# LEDs.net
KiCad netlist of a schematic drawn in EAGLE
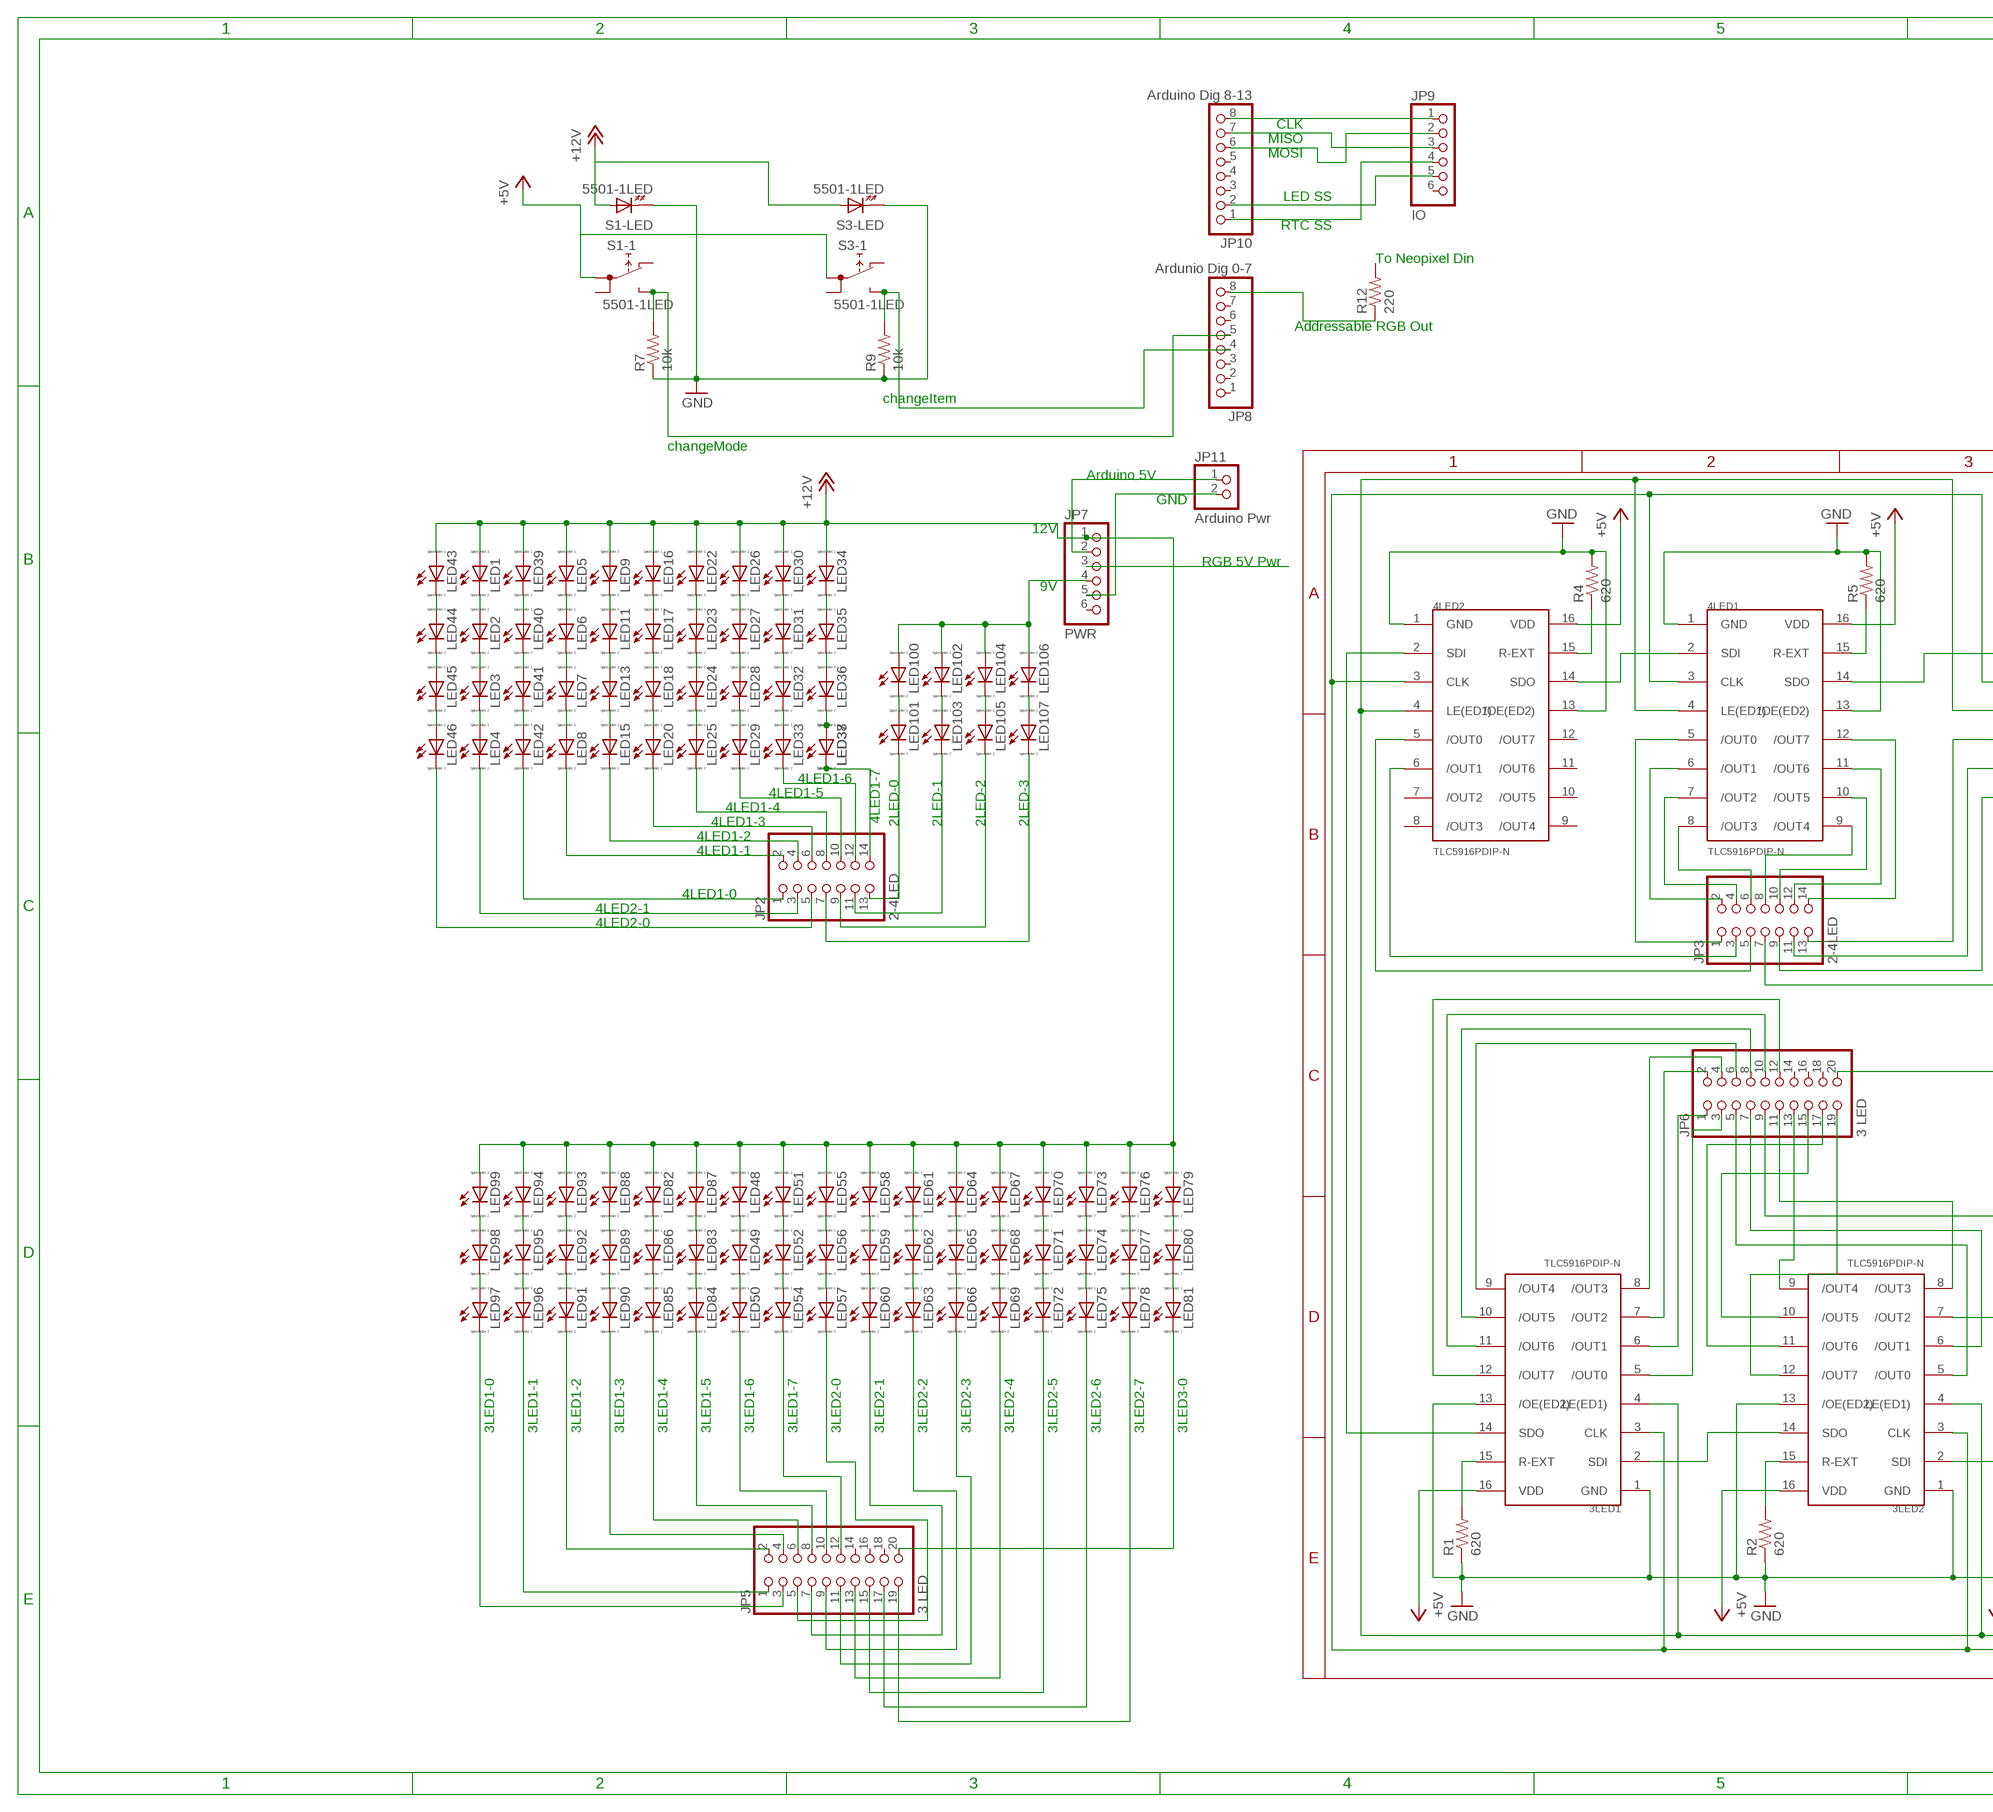
[diagram p0: schematic, sheet 1, part 1 of 2]
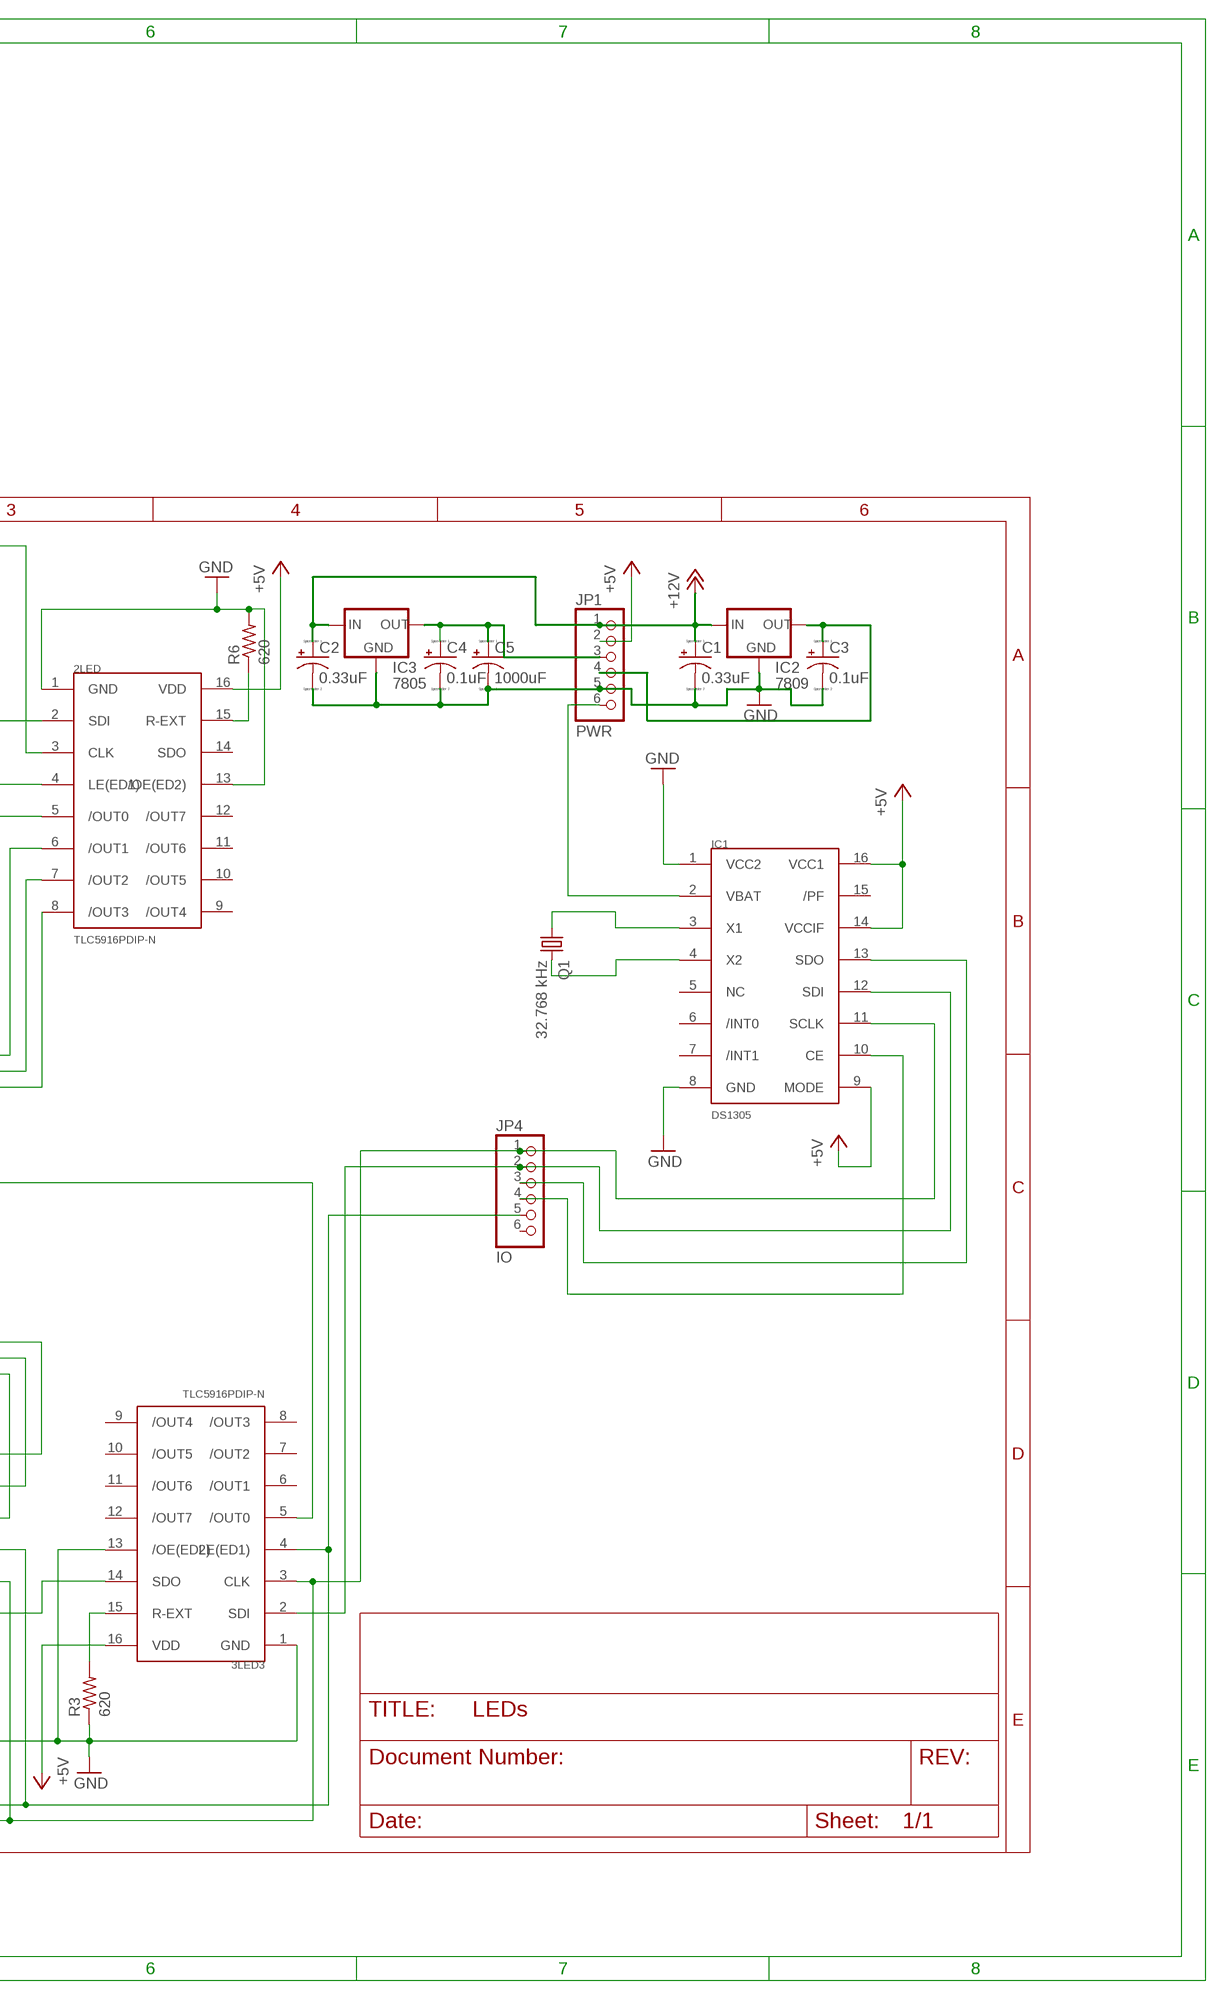
[diagram p1: schematic, sheet 1, part 2 of 2]

(export (version "E")
  (design (tool "Eeschema 10.0.6"))
  (components
    (comp (ref "2LED")
      (value "TLC5916PDIP-N")
      (footprint "eagle-import:DIL16")
      (libsource (lib "eagle-import") (part "TLC5916PDIP-N"))
    )
    (comp (ref "3LED1")
      (value "TLC5916PDIP-N")
      (footprint "eagle-import:DIL16")
      (libsource (lib "eagle-import") (part "TLC5916PDIP-N"))
    )
    (comp (ref "3LED2")
      (value "TLC5916PDIP-N")
      (footprint "eagle-import:DIL16")
      (libsource (lib "eagle-import") (part "TLC5916PDIP-N"))
    )
    (comp (ref "3LED3")
      (value "TLC5916PDIP-N")
      (footprint "eagle-import:DIL16")
      (libsource (lib "eagle-import") (part "TLC5916PDIP-N"))
    )
    (comp (ref "4LED1")
      (value "TLC5916PDIP-N")
      (footprint "eagle-import:DIL16")
      (libsource (lib "eagle-import") (part "TLC5916PDIP-N"))
    )
    (comp (ref "4LED2")
      (value "TLC5916PDIP-N")
      (footprint "eagle-import:DIL16")
      (libsource (lib "eagle-import") (part "TLC5916PDIP-N"))
    )
    (comp (ref "C1")
      (value "0.33uF")
      (footprint "eagle-import:E2-4")
      (libsource (lib "eagle-import") (part "CPOL-USE2-4"))
    )
    (comp (ref "C2")
      (value "0.33uF")
      (footprint "eagle-import:E2-4")
      (libsource (lib "eagle-import") (part "CPOL-USE2-4"))
    )
    (comp (ref "C3")
      (value "0.1uF")
      (footprint "eagle-import:E2-4")
      (libsource (lib "eagle-import") (part "CPOL-USE2-4"))
    )
    (comp (ref "C4")
      (value "0.1uF")
      (footprint "eagle-import:E2-4")
      (libsource (lib "eagle-import") (part "CPOL-USE2-4"))
    )
    (comp (ref "C5")
      (value "1000uF")
      (footprint "eagle-import:E3,5-8")
      (libsource (lib "eagle-import") (part "CPOL-USE3.5-8"))
    )
    (comp (ref "IC1")
      (value "DS1305")
      (footprint "eagle-import:DIL16")
      (libsource (lib "eagle-import") (part "DS1305"))
    )
    (comp (ref "IC2")
      (value "7809")
      (footprint "eagle-import:78XXL")
      (libsource (lib "eagle-import") (part "78XXL"))
    )
    (comp (ref "IC3")
      (value "7805")
      (footprint "eagle-import:78XXL")
      (libsource (lib "eagle-import") (part "78XXL"))
    )
    (comp (ref "JP1")
      (value "PWR")
      (footprint "eagle-import:1X06")
      (libsource (lib "eagle-import") (part "PINHD-1X6"))
    )
    (comp (ref "JP2")
      (value "2-4LED")
      (footprint "eagle-import:2X07")
      (libsource (lib "eagle-import") (part "PINHD-2X7"))
    )
    (comp (ref "JP3")
      (value "2-4LED")
      (footprint "eagle-import:2X07")
      (libsource (lib "eagle-import") (part "PINHD-2X7"))
    )
    (comp (ref "JP4")
      (value "IO")
      (footprint "eagle-import:1X06")
      (libsource (lib "eagle-import") (part "PINHD-1X6"))
    )
    (comp (ref "JP5")
      (value "3 LED")
      (footprint "eagle-import:2X10")
      (libsource (lib "eagle-import") (part "PINHD-2X10"))
    )
    (comp (ref "JP6")
      (value "3 LED")
      (footprint "eagle-import:2X10")
      (libsource (lib "eagle-import") (part "PINHD-2X10"))
    )
    (comp (ref "JP7")
      (value "PWR")
      (footprint "eagle-import:1X06")
      (libsource (lib "eagle-import") (part "PINHD-1X6"))
    )
    (comp (ref "JP8")
      (value "Ardunio Dig 0-7")
      (footprint "eagle-import:1X08")
      (libsource (lib "eagle-import") (part "PINHD-1X8"))
    )
    (comp (ref "JP9")
      (value "IO")
      (footprint "eagle-import:1X06")
      (libsource (lib "eagle-import") (part "PINHD-1X6"))
    )
    (comp (ref "JP10")
      (value "Arduino Dig 8-13")
      (footprint "eagle-import:1X08")
      (libsource (lib "eagle-import") (part "PINHD-1X8"))
    )
    (comp (ref "JP11")
      (value "Arduino Pwr")
      (footprint "eagle-import:1X02")
      (libsource (lib "eagle-import") (part "PINHD-1X2"))
    )
    (comp (ref "LED1")
      (value "LED_ELD260")
      (footprint "eagle-import:LED_LD260")
      (libsource (lib "eagle-import") (part "LED_ELD260"))
    )
    (comp (ref "LED2")
      (value "LED_ELD260")
      (footprint "eagle-import:LED_LD260")
      (libsource (lib "eagle-import") (part "LED_ELD260"))
    )
    (comp (ref "LED3")
      (value "LED_ELD260")
      (footprint "eagle-import:LED_LD260")
      (libsource (lib "eagle-import") (part "LED_ELD260"))
    )
    (comp (ref "LED4")
      (value "LED_ELD260")
      (footprint "eagle-import:LED_LD260")
      (libsource (lib "eagle-import") (part "LED_ELD260"))
    )
    (comp (ref "LED5")
      (value "LED_ELD260")
      (footprint "eagle-import:LED_LD260")
      (libsource (lib "eagle-import") (part "LED_ELD260"))
    )
    (comp (ref "LED6")
      (value "LED_ELD260")
      (footprint "eagle-import:LED_LD260")
      (libsource (lib "eagle-import") (part "LED_ELD260"))
    )
    (comp (ref "LED7")
      (value "LED_ELD260")
      (footprint "eagle-import:LED_LD260")
      (libsource (lib "eagle-import") (part "LED_ELD260"))
    )
    (comp (ref "LED8")
      (value "LED_ELD260")
      (footprint "eagle-import:LED_LD260")
      (libsource (lib "eagle-import") (part "LED_ELD260"))
    )
    (comp (ref "LED9")
      (value "LED_ELD260")
      (footprint "eagle-import:LED_LD260")
      (libsource (lib "eagle-import") (part "LED_ELD260"))
    )
    (comp (ref "LED11")
      (value "LED_ELD260")
      (footprint "eagle-import:LED_LD260")
      (libsource (lib "eagle-import") (part "LED_ELD260"))
    )
    (comp (ref "LED13")
      (value "LED_ELD260")
      (footprint "eagle-import:LED_LD260")
      (libsource (lib "eagle-import") (part "LED_ELD260"))
    )
    (comp (ref "LED15")
      (value "LED_ELD260")
      (footprint "eagle-import:LED_LD260")
      (libsource (lib "eagle-import") (part "LED_ELD260"))
    )
    (comp (ref "LED16")
      (value "LED_ELD260")
      (footprint "eagle-import:LED_LD260")
      (libsource (lib "eagle-import") (part "LED_ELD260"))
    )
    (comp (ref "LED17")
      (value "LED_ELD260")
      (footprint "eagle-import:LED_LD260")
      (libsource (lib "eagle-import") (part "LED_ELD260"))
    )
    (comp (ref "LED18")
      (value "LED_ELD260")
      (footprint "eagle-import:LED_LD260")
      (libsource (lib "eagle-import") (part "LED_ELD260"))
    )
    (comp (ref "LED20")
      (value "LED_ELD260")
      (footprint "eagle-import:LED_LD260")
      (libsource (lib "eagle-import") (part "LED_ELD260"))
    )
    (comp (ref "LED22")
      (value "LED_ELD260")
      (footprint "eagle-import:LED_LD260")
      (libsource (lib "eagle-import") (part "LED_ELD260"))
    )
    (comp (ref "LED23")
      (value "LED_ELD260")
      (footprint "eagle-import:LED_LD260")
      (libsource (lib "eagle-import") (part "LED_ELD260"))
    )
    (comp (ref "LED24")
      (value "LED_ELD260")
      (footprint "eagle-import:LED_LD260")
      (libsource (lib "eagle-import") (part "LED_ELD260"))
    )
    (comp (ref "LED25")
      (value "LED_ELD260")
      (footprint "eagle-import:LED_LD260")
      (libsource (lib "eagle-import") (part "LED_ELD260"))
    )
    (comp (ref "LED26")
      (value "LED_ELD260")
      (footprint "eagle-import:LED_LD260")
      (libsource (lib "eagle-import") (part "LED_ELD260"))
    )
    (comp (ref "LED27")
      (value "LED_ELD260")
      (footprint "eagle-import:LED_LD260")
      (libsource (lib "eagle-import") (part "LED_ELD260"))
    )
    (comp (ref "LED28")
      (value "LED_ELD260")
      (footprint "eagle-import:LED_LD260")
      (libsource (lib "eagle-import") (part "LED_ELD260"))
    )
    (comp (ref "LED29")
      (value "LED_ELD260")
      (footprint "eagle-import:LED_LD260")
      (libsource (lib "eagle-import") (part "LED_ELD260"))
    )
    (comp (ref "LED30")
      (value "LED_ELD260")
      (footprint "eagle-import:LED_LD260")
      (libsource (lib "eagle-import") (part "LED_ELD260"))
    )
    (comp (ref "LED31")
      (value "LED_ELD260")
      (footprint "eagle-import:LED_LD260")
      (libsource (lib "eagle-import") (part "LED_ELD260"))
    )
    (comp (ref "LED32")
      (value "LED_ELD260")
      (footprint "eagle-import:LED_LD260")
      (libsource (lib "eagle-import") (part "LED_ELD260"))
    )
    (comp (ref "LED33")
      (value "LED_ELD260")
      (footprint "eagle-import:LED_LD260")
      (libsource (lib "eagle-import") (part "LED_ELD260"))
    )
    (comp (ref "LED34")
      (value "LED_ELD260")
      (footprint "eagle-import:LED_LD260")
      (libsource (lib "eagle-import") (part "LED_ELD260"))
    )
    (comp (ref "LED35")
      (value "LED_ELD260")
      (footprint "eagle-import:LED_LD260")
      (libsource (lib "eagle-import") (part "LED_ELD260"))
    )
    (comp (ref "LED36")
      (value "LED_ELD260")
      (footprint "eagle-import:LED_LD260")
      (libsource (lib "eagle-import") (part "LED_ELD260"))
    )
    (comp (ref "LED37")
      (value "LED_ELD260")
      (footprint "eagle-import:LED_LD260")
      (libsource (lib "eagle-import") (part "LED_ELD260"))
    )
    (comp (ref "LED38")
      (value "LED_ELD260")
      (footprint "eagle-import:LED_LD260")
      (libsource (lib "eagle-import") (part "LED_ELD260"))
    )
    (comp (ref "LED39")
      (value "LED_ELD260")
      (footprint "eagle-import:LED_LD260")
      (libsource (lib "eagle-import") (part "LED_ELD260"))
    )
    (comp (ref "LED40")
      (value "LED_ELD260")
      (footprint "eagle-import:LED_LD260")
      (libsource (lib "eagle-import") (part "LED_ELD260"))
    )
    (comp (ref "LED41")
      (value "LED_ELD260")
      (footprint "eagle-import:LED_LD260")
      (libsource (lib "eagle-import") (part "LED_ELD260"))
    )
    (comp (ref "LED42")
      (value "LED_ELD260")
      (footprint "eagle-import:LED_LD260")
      (libsource (lib "eagle-import") (part "LED_ELD260"))
    )
    (comp (ref "LED43")
      (value "LED_ELD260")
      (footprint "eagle-import:LED_LD260")
      (libsource (lib "eagle-import") (part "LED_ELD260"))
    )
    (comp (ref "LED44")
      (value "LED_ELD260")
      (footprint "eagle-import:LED_LD260")
      (libsource (lib "eagle-import") (part "LED_ELD260"))
    )
    (comp (ref "LED45")
      (value "LED_ELD260")
      (footprint "eagle-import:LED_LD260")
      (libsource (lib "eagle-import") (part "LED_ELD260"))
    )
    (comp (ref "LED46")
      (value "LED_ELD260")
      (footprint "eagle-import:LED_LD260")
      (libsource (lib "eagle-import") (part "LED_ELD260"))
    )
    (comp (ref "LED48")
      (value "LED_ELD260")
      (footprint "eagle-import:LED_LD260")
      (libsource (lib "eagle-import") (part "LED_ELD260"))
    )
    (comp (ref "LED49")
      (value "LED_ELD260")
      (footprint "eagle-import:LED_LD260")
      (libsource (lib "eagle-import") (part "LED_ELD260"))
    )
    (comp (ref "LED50")
      (value "LED_ELD260")
      (footprint "eagle-import:LED_LD260")
      (libsource (lib "eagle-import") (part "LED_ELD260"))
    )
    (comp (ref "LED51")
      (value "LED_ELD260")
      (footprint "eagle-import:LED_LD260")
      (libsource (lib "eagle-import") (part "LED_ELD260"))
    )
    (comp (ref "LED52")
      (value "LED_ELD260")
      (footprint "eagle-import:LED_LD260")
      (libsource (lib "eagle-import") (part "LED_ELD260"))
    )
    (comp (ref "LED54")
      (value "LED_ELD260")
      (footprint "eagle-import:LED_LD260")
      (libsource (lib "eagle-import") (part "LED_ELD260"))
    )
    (comp (ref "LED55")
      (value "LED_ELD260")
      (footprint "eagle-import:LED_LD260")
      (libsource (lib "eagle-import") (part "LED_ELD260"))
    )
    (comp (ref "LED56")
      (value "LED_ELD260")
      (footprint "eagle-import:LED_LD260")
      (libsource (lib "eagle-import") (part "LED_ELD260"))
    )
    (comp (ref "LED57")
      (value "LED_ELD260")
      (footprint "eagle-import:LED_LD260")
      (libsource (lib "eagle-import") (part "LED_ELD260"))
    )
    (comp (ref "LED58")
      (value "LED_ELD260")
      (footprint "eagle-import:LED_LD260")
      (libsource (lib "eagle-import") (part "LED_ELD260"))
    )
    (comp (ref "LED59")
      (value "LED_ELD260")
      (footprint "eagle-import:LED_LD260")
      (libsource (lib "eagle-import") (part "LED_ELD260"))
    )
    (comp (ref "LED60")
      (value "LED_ELD260")
      (footprint "eagle-import:LED_LD260")
      (libsource (lib "eagle-import") (part "LED_ELD260"))
    )
    (comp (ref "LED61")
      (value "LED_ELD260")
      (footprint "eagle-import:LED_LD260")
      (libsource (lib "eagle-import") (part "LED_ELD260"))
    )
    (comp (ref "LED62")
      (value "LED_ELD260")
      (footprint "eagle-import:LED_LD260")
      (libsource (lib "eagle-import") (part "LED_ELD260"))
    )
    (comp (ref "LED63")
      (value "LED_ELD260")
      (footprint "eagle-import:LED_LD260")
      (libsource (lib "eagle-import") (part "LED_ELD260"))
    )
    (comp (ref "LED64")
      (value "LED_ELD260")
      (footprint "eagle-import:LED_LD260")
      (libsource (lib "eagle-import") (part "LED_ELD260"))
    )
    (comp (ref "LED65")
      (value "LED_ELD260")
      (footprint "eagle-import:LED_LD260")
      (libsource (lib "eagle-import") (part "LED_ELD260"))
    )
    (comp (ref "LED66")
      (value "LED_ELD260")
      (footprint "eagle-import:LED_LD260")
      (libsource (lib "eagle-import") (part "LED_ELD260"))
    )
    (comp (ref "LED67")
      (value "LED_ELD260")
      (footprint "eagle-import:LED_LD260")
      (libsource (lib "eagle-import") (part "LED_ELD260"))
    )
    (comp (ref "LED68")
      (value "LED_ELD260")
      (footprint "eagle-import:LED_LD260")
      (libsource (lib "eagle-import") (part "LED_ELD260"))
    )
    (comp (ref "LED69")
      (value "LED_ELD260")
      (footprint "eagle-import:LED_LD260")
      (libsource (lib "eagle-import") (part "LED_ELD260"))
    )
    (comp (ref "LED70")
      (value "LED_ELD260")
      (footprint "eagle-import:LED_LD260")
      (libsource (lib "eagle-import") (part "LED_ELD260"))
    )
    (comp (ref "LED71")
      (value "LED_ELD260")
      (footprint "eagle-import:LED_LD260")
      (libsource (lib "eagle-import") (part "LED_ELD260"))
    )
    (comp (ref "LED72")
      (value "LED_ELD260")
      (footprint "eagle-import:LED_LD260")
      (libsource (lib "eagle-import") (part "LED_ELD260"))
    )
    (comp (ref "LED73")
      (value "LED_ELD260")
      (footprint "eagle-import:LED_LD260")
      (libsource (lib "eagle-import") (part "LED_ELD260"))
    )
    (comp (ref "LED74")
      (value "LED_ELD260")
      (footprint "eagle-import:LED_LD260")
      (libsource (lib "eagle-import") (part "LED_ELD260"))
    )
    (comp (ref "LED75")
      (value "LED_ELD260")
      (footprint "eagle-import:LED_LD260")
      (libsource (lib "eagle-import") (part "LED_ELD260"))
    )
    (comp (ref "LED76")
      (value "LED_ELD260")
      (footprint "eagle-import:LED_LD260")
      (libsource (lib "eagle-import") (part "LED_ELD260"))
    )
    (comp (ref "LED77")
      (value "LED_ELD260")
      (footprint "eagle-import:LED_LD260")
      (libsource (lib "eagle-import") (part "LED_ELD260"))
    )
    (comp (ref "LED78")
      (value "LED_ELD260")
      (footprint "eagle-import:LED_LD260")
      (libsource (lib "eagle-import") (part "LED_ELD260"))
    )
    (comp (ref "LED79")
      (value "LED_ELD260")
      (footprint "eagle-import:LED_LD260")
      (libsource (lib "eagle-import") (part "LED_ELD260"))
    )
    (comp (ref "LED80")
      (value "LED_ELD260")
      (footprint "eagle-import:LED_LD260")
      (libsource (lib "eagle-import") (part "LED_ELD260"))
    )
    (comp (ref "LED81")
      (value "LED_ELD260")
      (footprint "eagle-import:LED_LD260")
      (libsource (lib "eagle-import") (part "LED_ELD260"))
    )
    (comp (ref "LED82")
      (value "LED_ELD260")
      (footprint "eagle-import:LED_LD260")
      (libsource (lib "eagle-import") (part "LED_ELD260"))
    )
    (comp (ref "LED83")
      (value "LED_ELD260")
      (footprint "eagle-import:LED_LD260")
      (libsource (lib "eagle-import") (part "LED_ELD260"))
    )
    (comp (ref "LED84")
      (value "LED_ELD260")
      (footprint "eagle-import:LED_LD260")
      (libsource (lib "eagle-import") (part "LED_ELD260"))
    )
    (comp (ref "LED85")
      (value "LED_ELD260")
      (footprint "eagle-import:LED_LD260")
      (libsource (lib "eagle-import") (part "LED_ELD260"))
    )
    (comp (ref "LED86")
      (value "LED_ELD260")
      (footprint "eagle-import:LED_LD260")
      (libsource (lib "eagle-import") (part "LED_ELD260"))
    )
    (comp (ref "LED87")
      (value "LED_ELD260")
      (footprint "eagle-import:LED_LD260")
      (libsource (lib "eagle-import") (part "LED_ELD260"))
    )
    (comp (ref "LED88")
      (value "LED_ELD260")
      (footprint "eagle-import:LED_LD260")
      (libsource (lib "eagle-import") (part "LED_ELD260"))
    )
    (comp (ref "LED89")
      (value "LED_ELD260")
      (footprint "eagle-import:LED_LD260")
      (libsource (lib "eagle-import") (part "LED_ELD260"))
    )
    (comp (ref "LED90")
      (value "LED_ELD260")
      (footprint "eagle-import:LED_LD260")
      (libsource (lib "eagle-import") (part "LED_ELD260"))
    )
    (comp (ref "LED91")
      (value "LED_ELD260")
      (footprint "eagle-import:LED_LD260")
      (libsource (lib "eagle-import") (part "LED_ELD260"))
    )
    (comp (ref "LED92")
      (value "LED_ELD260")
      (footprint "eagle-import:LED_LD260")
      (libsource (lib "eagle-import") (part "LED_ELD260"))
    )
    (comp (ref "LED93")
      (value "LED_ELD260")
      (footprint "eagle-import:LED_LD260")
      (libsource (lib "eagle-import") (part "LED_ELD260"))
    )
    (comp (ref "LED94")
      (value "LED_ELD260")
      (footprint "eagle-import:LED_LD260")
      (libsource (lib "eagle-import") (part "LED_ELD260"))
    )
    (comp (ref "LED95")
      (value "LED_ELD260")
      (footprint "eagle-import:LED_LD260")
      (libsource (lib "eagle-import") (part "LED_ELD260"))
    )
    (comp (ref "LED96")
      (value "LED_ELD260")
      (footprint "eagle-import:LED_LD260")
      (libsource (lib "eagle-import") (part "LED_ELD260"))
    )
    (comp (ref "LED97")
      (value "LED_ELD260")
      (footprint "eagle-import:LED_LD260")
      (libsource (lib "eagle-import") (part "LED_ELD260"))
    )
    (comp (ref "LED98")
      (value "LED_ELD260")
      (footprint "eagle-import:LED_LD260")
      (libsource (lib "eagle-import") (part "LED_ELD260"))
    )
    (comp (ref "LED99")
      (value "LED_ELD260")
      (footprint "eagle-import:LED_LD260")
      (libsource (lib "eagle-import") (part "LED_ELD260"))
    )
    (comp (ref "LED100")
      (value "LED_ELD260")
      (footprint "eagle-import:LED_LD260")
      (libsource (lib "eagle-import") (part "LED_ELD260"))
    )
    (comp (ref "LED101")
      (value "LED_ELD260")
      (footprint "eagle-import:LED_LD260")
      (libsource (lib "eagle-import") (part "LED_ELD260"))
    )
    (comp (ref "LED102")
      (value "LED_ELD260")
      (footprint "eagle-import:LED_LD260")
      (libsource (lib "eagle-import") (part "LED_ELD260"))
    )
    (comp (ref "LED103")
      (value "LED_ELD260")
      (footprint "eagle-import:LED_LD260")
      (libsource (lib "eagle-import") (part "LED_ELD260"))
    )
    (comp (ref "LED104")
      (value "LED_ELD260")
      (footprint "eagle-import:LED_LD260")
      (libsource (lib "eagle-import") (part "LED_ELD260"))
    )
    (comp (ref "LED105")
      (value "LED_ELD260")
      (footprint "eagle-import:LED_LD260")
      (libsource (lib "eagle-import") (part "LED_ELD260"))
    )
    (comp (ref "LED106")
      (value "LED_ELD260")
      (footprint "eagle-import:LED_LD260")
      (libsource (lib "eagle-import") (part "LED_ELD260"))
    )
    (comp (ref "LED107")
      (value "LED_ELD260")
      (footprint "eagle-import:LED_LD260")
      (libsource (lib "eagle-import") (part "LED_ELD260"))
    )
    (comp (ref "Q1")
      (value "32.768 kHz")
      (footprint "eagle-import:TC26V")
      (libsource (lib "eagle-import") (part "CRYSTALTC26V"))
    )
    (comp (ref "R1")
      (value "620")
      (footprint "eagle-import:V235_17")
      (libsource (lib "eagle-import") (part "R-US_V235/17"))
    )
    (comp (ref "R2")
      (value "620")
      (footprint "eagle-import:V235_17")
      (libsource (lib "eagle-import") (part "R-US_V235/17"))
    )
    (comp (ref "R3")
      (value "620")
      (footprint "eagle-import:V235_17")
      (libsource (lib "eagle-import") (part "R-US_V235/17"))
    )
    (comp (ref "R4")
      (value "620")
      (footprint "eagle-import:V235_17")
      (libsource (lib "eagle-import") (part "R-US_V235/17"))
    )
    (comp (ref "R5")
      (value "620")
      (footprint "eagle-import:V235_17")
      (libsource (lib "eagle-import") (part "R-US_V235/17"))
    )
    (comp (ref "R6")
      (value "620")
      (footprint "eagle-import:V235_17")
      (libsource (lib "eagle-import") (part "R-US_V235/17"))
    )
    (comp (ref "R7")
      (value "10k")
      (footprint "eagle-import:0204_7")
      (libsource (lib "eagle-import") (part "R-US_0204/7"))
    )
    (comp (ref "R9")
      (value "10k")
      (footprint "eagle-import:0204_7")
      (libsource (lib "eagle-import") (part "R-US_0204/7"))
    )
    (comp (ref "R12")
      (value "220")
      (footprint "eagle-import:0204_7")
      (libsource (lib "eagle-import") (part "R-US_0204/7"))
    )
    (comp (ref "S1")
      (value "5501-1LED")
      (footprint "eagle-import:5501-1LED")
      (libsource (lib "eagle-import") (part "55?-1LED01"))
    )
    (comp (ref "S3")
      (value "5501-1LED")
      (footprint "eagle-import:5501-1LED")
      (libsource (lib "eagle-import") (part "55?-1LED01"))
    )
  )
  (nets
    (net (code "1") (name "+5V") (class "Default")
      (node (ref "2LED") (pin "16") (pinfunction "VDD_16") (pintype "power_in"))
      (node (ref "3LED1") (pin "16") (pinfunction "VDD_16") (pintype "power_in"))
      (node (ref "3LED2") (pin "16") (pinfunction "VDD_16") (pintype "power_in"))
      (node (ref "3LED3") (pin "16") (pinfunction "VDD_16") (pintype "power_in"))
      (node (ref "4LED1") (pin "16") (pinfunction "VDD_16") (pintype "power_in"))
      (node (ref "4LED2") (pin "16") (pinfunction "VDD_16") (pintype "power_in"))
      (node (ref "IC1") (pin "14") (pinfunction "VCCIF_14") (pintype "power_in"))
      (node (ref "IC1") (pin "16") (pinfunction "VCC1_16") (pintype "power_in"))
      (node (ref "IC1") (pin "9") (pinfunction "MODE_9") (pintype "input"))
      (node (ref "JP1") (pin "2") (pinfunction "2_2") (pintype "passive"))
      (node (ref "S1") (pin "1A") (pinfunction "1A_1A") (pintype "passive"))
      (node (ref "S3") (pin "1A") (pinfunction "1A_1A") (pintype "passive"))
    )
    (net (code "2") (name "+12V") (class "Default")
      (node (ref "C1") (pin "+") (pinfunction "+_+") (pintype "passive"))
      (node (ref "C2") (pin "+") (pinfunction "+_+") (pintype "passive"))
      (node (ref "IC2") (pin "IN") (pinfunction "IN_IN") (pintype "input"))
      (node (ref "IC3") (pin "IN") (pinfunction "IN_IN") (pintype "input"))
      (node (ref "JP1") (pin "1") (pinfunction "1_1") (pintype "passive"))
      (node (ref "JP7") (pin "1") (pinfunction "1_1") (pintype "passive"))
      (node (ref "LED1") (pin "A") (pinfunction "A_A") (pintype "passive"))
      (node (ref "LED16") (pin "A") (pinfunction "A_A") (pintype "passive"))
      (node (ref "LED22") (pin "A") (pinfunction "A_A") (pintype "passive"))
      (node (ref "LED26") (pin "A") (pinfunction "A_A") (pintype "passive"))
      (node (ref "LED30") (pin "A") (pinfunction "A_A") (pintype "passive"))
      (node (ref "LED34") (pin "A") (pinfunction "A_A") (pintype "passive"))
      (node (ref "LED39") (pin "A") (pinfunction "A_A") (pintype "passive"))
      (node (ref "LED43") (pin "A") (pinfunction "A_A") (pintype "passive"))
      (node (ref "LED48") (pin "A") (pinfunction "A_A") (pintype "passive"))
      (node (ref "LED5") (pin "A") (pinfunction "A_A") (pintype "passive"))
      (node (ref "LED51") (pin "A") (pinfunction "A_A") (pintype "passive"))
      (node (ref "LED55") (pin "A") (pinfunction "A_A") (pintype "passive"))
      (node (ref "LED58") (pin "A") (pinfunction "A_A") (pintype "passive"))
      (node (ref "LED61") (pin "A") (pinfunction "A_A") (pintype "passive"))
      (node (ref "LED64") (pin "A") (pinfunction "A_A") (pintype "passive"))
      (node (ref "LED67") (pin "A") (pinfunction "A_A") (pintype "passive"))
      (node (ref "LED70") (pin "A") (pinfunction "A_A") (pintype "passive"))
      (node (ref "LED73") (pin "A") (pinfunction "A_A") (pintype "passive"))
      (node (ref "LED76") (pin "A") (pinfunction "A_A") (pintype "passive"))
      (node (ref "LED79") (pin "A") (pinfunction "A_A") (pintype "passive"))
      (node (ref "LED82") (pin "A") (pinfunction "A_A") (pintype "passive"))
      (node (ref "LED87") (pin "A") (pinfunction "A_A") (pintype "passive"))
      (node (ref "LED88") (pin "A") (pinfunction "A_A") (pintype "passive"))
      (node (ref "LED9") (pin "A") (pinfunction "A_A") (pintype "passive"))
      (node (ref "LED93") (pin "A") (pinfunction "A_A") (pintype "passive"))
      (node (ref "LED94") (pin "A") (pinfunction "A_A") (pintype "passive"))
      (node (ref "LED99") (pin "A") (pinfunction "A_A") (pintype "passive"))
      (node (ref "S1") (pin "+") (pinfunction "A_+") (pintype "passive"))
      (node (ref "S3") (pin "+") (pinfunction "A_+") (pintype "passive"))
    )
    (net (code "3") (name "GND") (class "Default")
      (node (ref "2LED") (pin "1") (pinfunction "GND_1") (pintype "power_in"))
      (node (ref "2LED") (pin "13") (pinfunction "/OE(ED2)_13") (pintype "input"))
      (node (ref "3LED1") (pin "1") (pinfunction "GND_1") (pintype "power_in"))
      (node (ref "3LED1") (pin "13") (pinfunction "/OE(ED2)_13") (pintype "input"))
      (node (ref "3LED2") (pin "1") (pinfunction "GND_1") (pintype "power_in"))
      (node (ref "3LED2") (pin "13") (pinfunction "/OE(ED2)_13") (pintype "input"))
      (node (ref "3LED3") (pin "1") (pinfunction "GND_1") (pintype "power_in"))
      (node (ref "3LED3") (pin "13") (pinfunction "/OE(ED2)_13") (pintype "input"))
      (node (ref "4LED1") (pin "1") (pinfunction "GND_1") (pintype "power_in"))
      (node (ref "4LED1") (pin "13") (pinfunction "/OE(ED2)_13") (pintype "input"))
      (node (ref "4LED2") (pin "1") (pinfunction "GND_1") (pintype "power_in"))
      (node (ref "4LED2") (pin "13") (pinfunction "/OE(ED2)_13") (pintype "input"))
      (node (ref "C1") (pin "-") (pinfunction "-_-") (pintype "passive"))
      (node (ref "C2") (pin "-") (pinfunction "-_-") (pintype "passive"))
      (node (ref "C3") (pin "-") (pinfunction "-_-") (pintype "passive"))
      (node (ref "C4") (pin "-") (pinfunction "-_-") (pintype "passive"))
      (node (ref "C5") (pin "-") (pinfunction "-_-") (pintype "passive"))
      (node (ref "IC1") (pin "1") (pinfunction "VCC2_1") (pintype "power_in"))
      (node (ref "IC1") (pin "8") (pinfunction "GND_8") (pintype "power_in"))
      (node (ref "IC2") (pin "GND") (pinfunction "GND_GND") (pintype "input"))
      (node (ref "IC3") (pin "GND") (pinfunction "GND_GND") (pintype "input"))
      (node (ref "JP1") (pin "5") (pinfunction "5_5") (pintype "passive"))
      (node (ref "R1") (pin "1") (pinfunction "1_1") (pintype "passive"))
      (node (ref "R2") (pin "1") (pinfunction "1_1") (pintype "passive"))
      (node (ref "R3") (pin "1") (pinfunction "1_1") (pintype "passive"))
      (node (ref "R4") (pin "2") (pinfunction "2_2") (pintype "passive"))
      (node (ref "R5") (pin "2") (pinfunction "2_2") (pintype "passive"))
      (node (ref "R6") (pin "2") (pinfunction "2_2") (pintype "passive"))
      (node (ref "R7") (pin "1") (pinfunction "1_1") (pintype "passive"))
      (node (ref "R9") (pin "1") (pinfunction "1_1") (pintype "passive"))
      (node (ref "S1") (pin "-") (pinfunction "K_-") (pintype "passive"))
      (node (ref "S3") (pin "-") (pinfunction "K_-") (pintype "passive"))
    )
    (net (code "4") (name "Net-(2LED-CLK)") (class "Default")
      (node (ref "2LED") (pin "3") (pinfunction "CLK_3") (pintype "input"))
      (node (ref "3LED1") (pin "3") (pinfunction "CLK_3") (pintype "input"))
      (node (ref "3LED2") (pin "3") (pinfunction "CLK_3") (pintype "input"))
      (node (ref "3LED3") (pin "3") (pinfunction "CLK_3") (pintype "input"))
      (node (ref "4LED1") (pin "3") (pinfunction "CLK_3") (pintype "input"))
      (node (ref "4LED2") (pin "3") (pinfunction "CLK_3") (pintype "input"))
      (node (ref "IC1") (pin "11") (pinfunction "SCLK_11") (pintype "input"))
      (node (ref "JP4") (pin "1") (pinfunction "1_1") (pintype "passive"))
    )
    (net (code "5") (name "Net-(2LED-LE(ED1))") (class "Default")
      (node (ref "2LED") (pin "4") (pinfunction "LE(ED1)_4") (pintype "input"))
      (node (ref "3LED1") (pin "4") (pinfunction "LE(ED1)_4") (pintype "input"))
      (node (ref "3LED2") (pin "4") (pinfunction "LE(ED1)_4") (pintype "input"))
      (node (ref "3LED3") (pin "4") (pinfunction "LE(ED1)_4") (pintype "input"))
      (node (ref "4LED1") (pin "4") (pinfunction "LE(ED1)_4") (pintype "input"))
      (node (ref "4LED2") (pin "4") (pinfunction "LE(ED1)_4") (pintype "input"))
      (node (ref "JP4") (pin "5") (pinfunction "5_5") (pintype "passive"))
    )
    (net (code "6") (name "Net-(2LED-R-EXT)") (class "Default")
      (node (ref "2LED") (pin "15") (pinfunction "R-EXT_15") (pintype "output"))
      (node (ref "R6") (pin "1") (pinfunction "1_1") (pintype "passive"))
    )
    (net (code "7") (name "Net-(2LED-SDI)") (class "Default")
      (node (ref "2LED") (pin "2") (pinfunction "SDI_2") (pintype "bidirectional"))
      (node (ref "4LED1") (pin "14") (pinfunction "SDO_14") (pintype "bidirectional"))
    )
    (net (code "8") (name "Net-(2LED-{slash}OUT0)") (class "Default")
      (node (ref "2LED") (pin "5") (pinfunction "/OUT0_5") (pintype "output"))
      (node (ref "JP3") (pin "13") (pinfunction "13_13") (pintype "passive"))
    )
    (net (code "9") (name "Net-(2LED-{slash}OUT1)") (class "Default")
      (node (ref "2LED") (pin "6") (pinfunction "/OUT1_6") (pintype "output"))
      (node (ref "JP3") (pin "11") (pinfunction "11_11") (pintype "passive"))
    )
    (net (code "10") (name "Net-(2LED-{slash}OUT2)") (class "Default")
      (node (ref "2LED") (pin "7") (pinfunction "/OUT2_7") (pintype "output"))
      (node (ref "JP3") (pin "9") (pinfunction "9_9") (pintype "passive"))
    )
    (net (code "11") (name "Net-(2LED-{slash}OUT3)") (class "Default")
      (node (ref "2LED") (pin "8") (pinfunction "/OUT3_8") (pintype "output"))
      (node (ref "JP3") (pin "7") (pinfunction "7_7") (pintype "passive"))
    )
    (net (code "12") (name "Net-(3LED1-R-EXT)") (class "Default")
      (node (ref "3LED1") (pin "15") (pinfunction "R-EXT_15") (pintype "output"))
      (node (ref "R1") (pin "2") (pinfunction "2_2") (pintype "passive"))
    )
    (net (code "13") (name "Net-(3LED1-SDI)") (class "Default")
      (node (ref "3LED1") (pin "2") (pinfunction "SDI_2") (pintype "bidirectional"))
      (node (ref "3LED2") (pin "14") (pinfunction "SDO_14") (pintype "bidirectional"))
    )
    (net (code "14") (name "Net-(3LED1-SDO)") (class "Default")
      (node (ref "3LED1") (pin "14") (pinfunction "SDO_14") (pintype "bidirectional"))
      (node (ref "4LED2") (pin "2") (pinfunction "SDI_2") (pintype "bidirectional"))
    )
    (net (code "15") (name "Net-(3LED1-{slash}OUT0)") (class "Default")
      (node (ref "3LED1") (pin "5") (pinfunction "/OUT0_5") (pintype "output"))
      (node (ref "JP6") (pin "3") (pinfunction "3_3") (pintype "passive"))
    )
    (net (code "16") (name "Net-(3LED1-{slash}OUT1)") (class "Default")
      (node (ref "3LED1") (pin "6") (pinfunction "/OUT1_6") (pintype "output"))
      (node (ref "JP6") (pin "1") (pinfunction "1_1") (pintype "passive"))
    )
    (net (code "17") (name "Net-(3LED1-{slash}OUT2)") (class "Default")
      (node (ref "3LED1") (pin "7") (pinfunction "/OUT2_7") (pintype "output"))
      (node (ref "JP6") (pin "2") (pinfunction "2_2") (pintype "passive"))
    )
    (net (code "18") (name "Net-(3LED1-{slash}OUT3)") (class "Default")
      (node (ref "3LED1") (pin "8") (pinfunction "/OUT3_8") (pintype "output"))
      (node (ref "JP6") (pin "4") (pinfunction "4_4") (pintype "passive"))
    )
    (net (code "19") (name "Net-(3LED1-{slash}OUT4)") (class "Default")
      (node (ref "3LED1") (pin "9") (pinfunction "/OUT4_9") (pintype "output"))
      (node (ref "JP6") (pin "6") (pinfunction "6_6") (pintype "passive"))
    )
    (net (code "20") (name "Net-(3LED1-{slash}OUT5)") (class "Default")
      (node (ref "3LED1") (pin "10") (pinfunction "/OUT5_10") (pintype "output"))
      (node (ref "JP6") (pin "8") (pinfunction "8_8") (pintype "passive"))
    )
    (net (code "21") (name "Net-(3LED1-{slash}OUT6)") (class "Default")
      (node (ref "3LED1") (pin "11") (pinfunction "/OUT6_11") (pintype "output"))
      (node (ref "JP6") (pin "10") (pinfunction "10_10") (pintype "passive"))
    )
    (net (code "22") (name "Net-(3LED1-{slash}OUT7)") (class "Default")
      (node (ref "3LED1") (pin "12") (pinfunction "/OUT7_12") (pintype "output"))
      (node (ref "JP6") (pin "12") (pinfunction "12_12") (pintype "passive"))
    )
    (net (code "23") (name "Net-(3LED2-R-EXT)") (class "Default")
      (node (ref "3LED2") (pin "15") (pinfunction "R-EXT_15") (pintype "output"))
      (node (ref "R2") (pin "2") (pinfunction "2_2") (pintype "passive"))
    )
    (net (code "24") (name "Net-(3LED2-SDI)") (class "Default")
      (node (ref "3LED2") (pin "2") (pinfunction "SDI_2") (pintype "bidirectional"))
      (node (ref "3LED3") (pin "14") (pinfunction "SDO_14") (pintype "bidirectional"))
    )
    (net (code "25") (name "Net-(3LED2-{slash}OUT0)") (class "Default")
      (node (ref "3LED2") (pin "5") (pinfunction "/OUT0_5") (pintype "output"))
      (node (ref "JP6") (pin "5") (pinfunction "5_5") (pintype "passive"))
    )
    (net (code "26") (name "Net-(3LED2-{slash}OUT1)") (class "Default")
      (node (ref "3LED2") (pin "6") (pinfunction "/OUT1_6") (pintype "output"))
      (node (ref "JP6") (pin "7") (pinfunction "7_7") (pintype "passive"))
    )
    (net (code "27") (name "Net-(3LED2-{slash}OUT2)") (class "Default")
      (node (ref "3LED2") (pin "7") (pinfunction "/OUT2_7") (pintype "output"))
      (node (ref "JP6") (pin "9") (pinfunction "9_9") (pintype "passive"))
    )
    (net (code "28") (name "Net-(3LED2-{slash}OUT3)") (class "Default")
      (node (ref "3LED2") (pin "8") (pinfunction "/OUT3_8") (pintype "output"))
      (node (ref "JP6") (pin "11") (pinfunction "11_11") (pintype "passive"))
    )
    (net (code "29") (name "Net-(3LED2-{slash}OUT4)") (class "Default")
      (node (ref "3LED2") (pin "9") (pinfunction "/OUT4_9") (pintype "output"))
      (node (ref "JP6") (pin "13") (pinfunction "13_13") (pintype "passive"))
    )
    (net (code "30") (name "Net-(3LED2-{slash}OUT5)") (class "Default")
      (node (ref "3LED2") (pin "10") (pinfunction "/OUT5_10") (pintype "output"))
      (node (ref "JP6") (pin "15") (pinfunction "15_15") (pintype "passive"))
    )
    (net (code "31") (name "Net-(3LED2-{slash}OUT6)") (class "Default")
      (node (ref "3LED2") (pin "11") (pinfunction "/OUT6_11") (pintype "output"))
      (node (ref "JP6") (pin "17") (pinfunction "17_17") (pintype "passive"))
    )
    (net (code "32") (name "Net-(3LED2-{slash}OUT7)") (class "Default")
      (node (ref "3LED2") (pin "12") (pinfunction "/OUT7_12") (pintype "output"))
      (node (ref "JP6") (pin "19") (pinfunction "19_19") (pintype "passive"))
    )
    (net (code "33") (name "Net-(3LED3-R-EXT)") (class "Default")
      (node (ref "3LED3") (pin "15") (pinfunction "R-EXT_15") (pintype "output"))
      (node (ref "R3") (pin "2") (pinfunction "2_2") (pintype "passive"))
    )
    (net (code "34") (name "Net-(3LED3-SDI)") (class "Default")
      (node (ref "3LED3") (pin "2") (pinfunction "SDI_2") (pintype "bidirectional"))
      (node (ref "IC1") (pin "12") (pinfunction "SDI_12") (pintype "input"))
      (node (ref "JP4") (pin "2") (pinfunction "2_2") (pintype "passive"))
    )
    (net (code "35") (name "Net-(3LED3-{slash}OUT0)") (class "Default")
      (node (ref "3LED3") (pin "5") (pinfunction "/OUT0_5") (pintype "output"))
      (node (ref "JP6") (pin "20") (pinfunction "20_20") (pintype "passive"))
    )
    (net (code "36") (name "Net-(4LED1-R-EXT)") (class "Default")
      (node (ref "4LED1") (pin "15") (pinfunction "R-EXT_15") (pintype "output"))
      (node (ref "R5") (pin "1") (pinfunction "1_1") (pintype "passive"))
    )
    (net (code "37") (name "Net-(4LED1-SDI)") (class "Default")
      (node (ref "4LED1") (pin "2") (pinfunction "SDI_2") (pintype "bidirectional"))
      (node (ref "4LED2") (pin "14") (pinfunction "SDO_14") (pintype "bidirectional"))
    )
    (net (code "38") (name "Net-(4LED1-{slash}OUT0)") (class "Default")
      (node (ref "4LED1") (pin "5") (pinfunction "/OUT0_5") (pintype "output"))
      (node (ref "JP3") (pin "1") (pinfunction "1_1") (pintype "passive"))
    )
    (net (code "39") (name "Net-(4LED1-{slash}OUT1)") (class "Default")
      (node (ref "4LED1") (pin "6") (pinfunction "/OUT1_6") (pintype "output"))
      (node (ref "JP3") (pin "2") (pinfunction "2_2") (pintype "passive"))
    )
    (net (code "40") (name "Net-(4LED1-{slash}OUT2)") (class "Default")
      (node (ref "4LED1") (pin "7") (pinfunction "/OUT2_7") (pintype "output"))
      (node (ref "JP3") (pin "4") (pinfunction "4_4") (pintype "passive"))
    )
    (net (code "41") (name "Net-(4LED1-{slash}OUT3)") (class "Default")
      (node (ref "4LED1") (pin "8") (pinfunction "/OUT3_8") (pintype "output"))
      (node (ref "JP3") (pin "6") (pinfunction "6_6") (pintype "passive"))
    )
    (net (code "42") (name "Net-(4LED1-{slash}OUT4)") (class "Default")
      (node (ref "4LED1") (pin "9") (pinfunction "/OUT4_9") (pintype "output"))
      (node (ref "JP3") (pin "8") (pinfunction "8_8") (pintype "passive"))
    )
    (net (code "43") (name "Net-(4LED1-{slash}OUT5)") (class "Default")
      (node (ref "4LED1") (pin "10") (pinfunction "/OUT5_10") (pintype "output"))
      (node (ref "JP3") (pin "10") (pinfunction "10_10") (pintype "passive"))
    )
    (net (code "44") (name "Net-(4LED1-{slash}OUT6)") (class "Default")
      (node (ref "4LED1") (pin "11") (pinfunction "/OUT6_11") (pintype "output"))
      (node (ref "JP3") (pin "12") (pinfunction "12_12") (pintype "passive"))
    )
    (net (code "45") (name "Net-(4LED1-{slash}OUT7)") (class "Default")
      (node (ref "4LED1") (pin "12") (pinfunction "/OUT7_12") (pintype "output"))
      (node (ref "JP3") (pin "14") (pinfunction "14_14") (pintype "passive"))
    )
    (net (code "46") (name "Net-(4LED2-R-EXT)") (class "Default")
      (node (ref "4LED2") (pin "15") (pinfunction "R-EXT_15") (pintype "output"))
      (node (ref "R4") (pin "1") (pinfunction "1_1") (pintype "passive"))
    )
    (net (code "47") (name "Net-(4LED2-{slash}OUT0)") (class "Default")
      (node (ref "4LED2") (pin "5") (pinfunction "/OUT0_5") (pintype "output"))
      (node (ref "JP3") (pin "5") (pinfunction "5_5") (pintype "passive"))
    )
    (net (code "48") (name "Net-(4LED2-{slash}OUT1)") (class "Default")
      (node (ref "4LED2") (pin "6") (pinfunction "/OUT1_6") (pintype "output"))
      (node (ref "JP3") (pin "3") (pinfunction "3_3") (pintype "passive"))
    )
    (net (code "49") (name "Net-(C3-Pad+)") (class "Default")
      (node (ref "C3") (pin "+") (pinfunction "+_+") (pintype "passive"))
      (node (ref "IC2") (pin "OUT") (pinfunction "OUT_OUT") (pintype "passive"))
      (node (ref "JP1") (pin "4") (pinfunction "4_4") (pintype "passive"))
    )
    (net (code "50") (name "Net-(C4-Pad+)") (class "Default")
      (node (ref "C4") (pin "+") (pinfunction "+_+") (pintype "passive"))
      (node (ref "C5") (pin "+") (pinfunction "+_+") (pintype "passive"))
      (node (ref "IC3") (pin "OUT") (pinfunction "OUT_OUT") (pintype "passive"))
      (node (ref "JP1") (pin "3") (pinfunction "3_3") (pintype "passive"))
    )
    (net (code "51") (name "Net-(IC1-CE)") (class "Default")
      (node (ref "IC1") (pin "10") (pinfunction "CE_10") (pintype "input"))
      (node (ref "JP4") (pin "4") (pinfunction "4_4") (pintype "passive"))
    )
    (net (code "52") (name "Net-(IC1-SDO)") (class "Default")
      (node (ref "IC1") (pin "13") (pinfunction "SDO_13") (pintype "output"))
      (node (ref "JP4") (pin "3") (pinfunction "3_3") (pintype "passive"))
    )
    (net (code "53") (name "Net-(IC1-VBAT)") (class "Default")
      (node (ref "IC1") (pin "2") (pinfunction "VBAT_2") (pintype "power_in"))
      (node (ref "JP1") (pin "6") (pinfunction "6_6") (pintype "passive"))
    )
    (net (code "54") (name "Net-(IC1-X1)") (class "Default")
      (node (ref "IC1") (pin "3") (pinfunction "X1_3") (pintype "input"))
      (node (ref "Q1") (pin "1") (pinfunction "1_1") (pintype "passive"))
    )
    (net (code "55") (name "Net-(IC1-X2)") (class "Default")
      (node (ref "IC1") (pin "4") (pinfunction "X2_4") (pintype "output"))
      (node (ref "Q1") (pin "2") (pinfunction "2_2") (pintype "passive"))
    )
    (net (code "56") (name "Net-(JP7-Pad4)") (class "Default")
      (node (ref "JP7") (pin "4") (pinfunction "4_4") (pintype "passive"))
      (node (ref "LED100") (pin "A") (pinfunction "A_A") (pintype "passive"))
      (node (ref "LED102") (pin "A") (pinfunction "A_A") (pintype "passive"))
      (node (ref "LED104") (pin "A") (pinfunction "A_A") (pintype "passive"))
      (node (ref "LED106") (pin "A") (pinfunction "A_A") (pintype "passive"))
    )
    (net (code "57") (name "Net-(JP8-Pad4)") (class "Default")
      (node (ref "JP8") (pin "4") (pinfunction "4_4") (pintype "passive"))
      (node (ref "R9") (pin "2") (pinfunction "2_2") (pintype "passive"))
      (node (ref "S3") (pin "NO") (pinfunction "NO_NO") (pintype "passive"))
    )
    (net (code "58") (name "Net-(JP8-Pad5)") (class "Default")
      (node (ref "JP8") (pin "5") (pinfunction "5_5") (pintype "passive"))
      (node (ref "R7") (pin "2") (pinfunction "2_2") (pintype "passive"))
      (node (ref "S1") (pin "NO") (pinfunction "NO_NO") (pintype "passive"))
    )
    (net (code "59") (name "Net-(JP8-Pad8)") (class "Default")
      (node (ref "JP8") (pin "8") (pinfunction "8_8") (pintype "passive"))
      (node (ref "R12") (pin "1") (pinfunction "1_1") (pintype "passive"))
    )
    (net (code "60") (name "Net-(JP10-Pad1)") (class "Default")
      (node (ref "JP10") (pin "1") (pinfunction "1_1") (pintype "passive"))
      (node (ref "JP9") (pin "4") (pinfunction "4_4") (pintype "passive"))
    )
    (net (code "61") (name "Net-(JP10-Pad2)") (class "Default")
      (node (ref "JP10") (pin "2") (pinfunction "2_2") (pintype "passive"))
      (node (ref "JP9") (pin "5") (pinfunction "5_5") (pintype "passive"))
    )
    (net (code "62") (name "Net-(JP10-Pad6)") (class "Default")
      (node (ref "JP10") (pin "6") (pinfunction "6_6") (pintype "passive"))
      (node (ref "JP9") (pin "2") (pinfunction "2_2") (pintype "passive"))
    )
    (net (code "63") (name "Net-(JP10-Pad7)") (class "Default")
      (node (ref "JP10") (pin "7") (pinfunction "7_7") (pintype "passive"))
      (node (ref "JP9") (pin "3") (pinfunction "3_3") (pintype "passive"))
    )
    (net (code "64") (name "Net-(JP10-Pad8)") (class "Default")
      (node (ref "JP10") (pin "8") (pinfunction "8_8") (pintype "passive"))
      (node (ref "JP9") (pin "1") (pinfunction "1_1") (pintype "passive"))
    )
    (net (code "65") (name "Net-(JP11-Pad1)") (class "Default")
      (node (ref "JP11") (pin "1") (pinfunction "1_1") (pintype "passive"))
      (node (ref "JP7") (pin "2") (pinfunction "2_2") (pintype "passive"))
    )
    (net (code "66") (name "Net-(JP11-Pad2)") (class "Default")
      (node (ref "JP11") (pin "2") (pinfunction "2_2") (pintype "passive"))
      (node (ref "JP7") (pin "5") (pinfunction "5_5") (pintype "passive"))
    )
    (net (code "67") (name "Net-(LED1-C)") (class "Default")
      (node (ref "LED1") (pin "K") (pinfunction "C_K") (pintype "passive"))
      (node (ref "LED2") (pin "A") (pinfunction "A_A") (pintype "passive"))
    )
    (net (code "68") (name "Net-(LED2-C)") (class "Default")
      (node (ref "LED2") (pin "K") (pinfunction "C_K") (pintype "passive"))
      (node (ref "LED3") (pin "A") (pinfunction "A_A") (pintype "passive"))
    )
    (net (code "69") (name "Net-(LED3-C)") (class "Default")
      (node (ref "LED3") (pin "K") (pinfunction "C_K") (pintype "passive"))
      (node (ref "LED4") (pin "A") (pinfunction "A_A") (pintype "passive"))
    )
    (net (code "70") (name "Net-(LED4-C)") (class "Default")
      (node (ref "JP2") (pin "3") (pinfunction "3_3") (pintype "passive"))
      (node (ref "LED4") (pin "K") (pinfunction "C_K") (pintype "passive"))
    )
    (net (code "71") (name "Net-(LED5-C)") (class "Default")
      (node (ref "LED5") (pin "K") (pinfunction "C_K") (pintype "passive"))
      (node (ref "LED6") (pin "A") (pinfunction "A_A") (pintype "passive"))
    )
    (net (code "72") (name "Net-(LED6-C)") (class "Default")
      (node (ref "LED6") (pin "K") (pinfunction "C_K") (pintype "passive"))
      (node (ref "LED7") (pin "A") (pinfunction "A_A") (pintype "passive"))
    )
    (net (code "73") (name "Net-(LED7-C)") (class "Default")
      (node (ref "LED7") (pin "K") (pinfunction "C_K") (pintype "passive"))
      (node (ref "LED8") (pin "A") (pinfunction "A_A") (pintype "passive"))
    )
    (net (code "74") (name "Net-(LED8-C)") (class "Default")
      (node (ref "JP2") (pin "2") (pinfunction "2_2") (pintype "passive"))
      (node (ref "LED8") (pin "K") (pinfunction "C_K") (pintype "passive"))
    )
    (net (code "75") (name "Net-(LED9-C)") (class "Default")
      (node (ref "LED11") (pin "A") (pinfunction "A_A") (pintype "passive"))
      (node (ref "LED9") (pin "K") (pinfunction "C_K") (pintype "passive"))
    )
    (net (code "76") (name "Net-(LED11-C)") (class "Default")
      (node (ref "LED11") (pin "K") (pinfunction "C_K") (pintype "passive"))
      (node (ref "LED13") (pin "A") (pinfunction "A_A") (pintype "passive"))
    )
    (net (code "77") (name "Net-(LED13-C)") (class "Default")
      (node (ref "LED13") (pin "K") (pinfunction "C_K") (pintype "passive"))
      (node (ref "LED15") (pin "A") (pinfunction "A_A") (pintype "passive"))
    )
    (net (code "78") (name "Net-(LED15-C)") (class "Default")
      (node (ref "JP2") (pin "4") (pinfunction "4_4") (pintype "passive"))
      (node (ref "LED15") (pin "K") (pinfunction "C_K") (pintype "passive"))
    )
    (net (code "79") (name "Net-(LED16-C)") (class "Default")
      (node (ref "LED16") (pin "K") (pinfunction "C_K") (pintype "passive"))
      (node (ref "LED17") (pin "A") (pinfunction "A_A") (pintype "passive"))
    )
    (net (code "80") (name "Net-(LED17-C)") (class "Default")
      (node (ref "LED17") (pin "K") (pinfunction "C_K") (pintype "passive"))
      (node (ref "LED18") (pin "A") (pinfunction "A_A") (pintype "passive"))
    )
    (net (code "81") (name "Net-(LED18-C)") (class "Default")
      (node (ref "LED18") (pin "K") (pinfunction "C_K") (pintype "passive"))
      (node (ref "LED20") (pin "A") (pinfunction "A_A") (pintype "passive"))
    )
    (net (code "82") (name "Net-(LED20-C)") (class "Default")
      (node (ref "JP2") (pin "6") (pinfunction "6_6") (pintype "passive"))
      (node (ref "LED20") (pin "K") (pinfunction "C_K") (pintype "passive"))
    )
    (net (code "83") (name "Net-(LED22-C)") (class "Default")
      (node (ref "LED22") (pin "K") (pinfunction "C_K") (pintype "passive"))
      (node (ref "LED23") (pin "A") (pinfunction "A_A") (pintype "passive"))
    )
    (net (code "84") (name "Net-(LED23-C)") (class "Default")
      (node (ref "LED23") (pin "K") (pinfunction "C_K") (pintype "passive"))
      (node (ref "LED24") (pin "A") (pinfunction "A_A") (pintype "passive"))
    )
    (net (code "85") (name "Net-(LED24-C)") (class "Default")
      (node (ref "LED24") (pin "K") (pinfunction "C_K") (pintype "passive"))
      (node (ref "LED25") (pin "A") (pinfunction "A_A") (pintype "passive"))
    )
    (net (code "86") (name "Net-(LED25-C)") (class "Default")
      (node (ref "JP2") (pin "8") (pinfunction "8_8") (pintype "passive"))
      (node (ref "LED25") (pin "K") (pinfunction "C_K") (pintype "passive"))
    )
    (net (code "87") (name "Net-(LED26-C)") (class "Default")
      (node (ref "LED26") (pin "K") (pinfunction "C_K") (pintype "passive"))
      (node (ref "LED27") (pin "A") (pinfunction "A_A") (pintype "passive"))
    )
    (net (code "88") (name "Net-(LED27-C)") (class "Default")
      (node (ref "LED27") (pin "K") (pinfunction "C_K") (pintype "passive"))
      (node (ref "LED28") (pin "A") (pinfunction "A_A") (pintype "passive"))
    )
    (net (code "89") (name "Net-(LED28-C)") (class "Default")
      (node (ref "LED28") (pin "K") (pinfunction "C_K") (pintype "passive"))
      (node (ref "LED29") (pin "A") (pinfunction "A_A") (pintype "passive"))
    )
    (net (code "90") (name "Net-(LED29-C)") (class "Default")
      (node (ref "JP2") (pin "10") (pinfunction "10_10") (pintype "passive"))
      (node (ref "LED29") (pin "K") (pinfunction "C_K") (pintype "passive"))
    )
    (net (code "91") (name "Net-(LED30-C)") (class "Default")
      (node (ref "LED30") (pin "K") (pinfunction "C_K") (pintype "passive"))
      (node (ref "LED31") (pin "A") (pinfunction "A_A") (pintype "passive"))
    )
    (net (code "92") (name "Net-(LED31-C)") (class "Default")
      (node (ref "LED31") (pin "K") (pinfunction "C_K") (pintype "passive"))
      (node (ref "LED32") (pin "A") (pinfunction "A_A") (pintype "passive"))
    )
    (net (code "93") (name "Net-(LED32-C)") (class "Default")
      (node (ref "LED32") (pin "K") (pinfunction "C_K") (pintype "passive"))
      (node (ref "LED33") (pin "A") (pinfunction "A_A") (pintype "passive"))
    )
    (net (code "94") (name "Net-(LED33-C)") (class "Default")
      (node (ref "JP2") (pin "12") (pinfunction "12_12") (pintype "passive"))
      (node (ref "LED33") (pin "K") (pinfunction "C_K") (pintype "passive"))
    )
    (net (code "95") (name "Net-(LED34-C)") (class "Default")
      (node (ref "LED34") (pin "K") (pinfunction "C_K") (pintype "passive"))
      (node (ref "LED35") (pin "A") (pinfunction "A_A") (pintype "passive"))
    )
    (net (code "96") (name "Net-(LED35-C)") (class "Default")
      (node (ref "LED35") (pin "K") (pinfunction "C_K") (pintype "passive"))
      (node (ref "LED36") (pin "A") (pinfunction "A_A") (pintype "passive"))
    )
    (net (code "97") (name "Net-(LED36-C)") (class "Default")
      (node (ref "LED36") (pin "K") (pinfunction "C_K") (pintype "passive"))
      (node (ref "LED37") (pin "A") (pinfunction "A_A") (pintype "passive"))
      (node (ref "LED38") (pin "A") (pinfunction "A_A") (pintype "passive"))
    )
    (net (code "98") (name "Net-(LED37-C)") (class "Default")
      (node (ref "JP2") (pin "14") (pinfunction "14_14") (pintype "passive"))
      (node (ref "LED37") (pin "K") (pinfunction "C_K") (pintype "passive"))
      (node (ref "LED38") (pin "K") (pinfunction "C_K") (pintype "passive"))
    )
    (net (code "99") (name "Net-(LED39-C)") (class "Default")
      (node (ref "LED39") (pin "K") (pinfunction "C_K") (pintype "passive"))
      (node (ref "LED40") (pin "A") (pinfunction "A_A") (pintype "passive"))
    )
    (net (code "100") (name "Net-(LED40-C)") (class "Default")
      (node (ref "LED40") (pin "K") (pinfunction "C_K") (pintype "passive"))
      (node (ref "LED41") (pin "A") (pinfunction "A_A") (pintype "passive"))
    )
    (net (code "101") (name "Net-(LED41-C)") (class "Default")
      (node (ref "LED41") (pin "K") (pinfunction "C_K") (pintype "passive"))
      (node (ref "LED42") (pin "A") (pinfunction "A_A") (pintype "passive"))
    )
    (net (code "102") (name "Net-(LED42-C)") (class "Default")
      (node (ref "JP2") (pin "1") (pinfunction "1_1") (pintype "passive"))
      (node (ref "LED42") (pin "K") (pinfunction "C_K") (pintype "passive"))
    )
    (net (code "103") (name "Net-(LED43-C)") (class "Default")
      (node (ref "LED43") (pin "K") (pinfunction "C_K") (pintype "passive"))
      (node (ref "LED44") (pin "A") (pinfunction "A_A") (pintype "passive"))
    )
    (net (code "104") (name "Net-(LED44-C)") (class "Default")
      (node (ref "LED44") (pin "K") (pinfunction "C_K") (pintype "passive"))
      (node (ref "LED45") (pin "A") (pinfunction "A_A") (pintype "passive"))
    )
    (net (code "105") (name "Net-(LED45-C)") (class "Default")
      (node (ref "LED45") (pin "K") (pinfunction "C_K") (pintype "passive"))
      (node (ref "LED46") (pin "A") (pinfunction "A_A") (pintype "passive"))
    )
    (net (code "106") (name "Net-(LED46-C)") (class "Default")
      (node (ref "JP2") (pin "5") (pinfunction "5_5") (pintype "passive"))
      (node (ref "LED46") (pin "K") (pinfunction "C_K") (pintype "passive"))
    )
    (net (code "107") (name "Net-(LED48-C)") (class "Default")
      (node (ref "LED48") (pin "K") (pinfunction "C_K") (pintype "passive"))
      (node (ref "LED49") (pin "A") (pinfunction "A_A") (pintype "passive"))
    )
    (net (code "108") (name "Net-(LED49-C)") (class "Default")
      (node (ref "LED49") (pin "K") (pinfunction "C_K") (pintype "passive"))
      (node (ref "LED50") (pin "A") (pinfunction "A_A") (pintype "passive"))
    )
    (net (code "109") (name "Net-(LED50-C)") (class "Default")
      (node (ref "JP5") (pin "10") (pinfunction "10_10") (pintype "passive"))
      (node (ref "LED50") (pin "K") (pinfunction "C_K") (pintype "passive"))
    )
    (net (code "110") (name "Net-(LED51-C)") (class "Default")
      (node (ref "LED51") (pin "K") (pinfunction "C_K") (pintype "passive"))
      (node (ref "LED52") (pin "A") (pinfunction "A_A") (pintype "passive"))
    )
    (net (code "111") (name "Net-(LED52-C)") (class "Default")
      (node (ref "LED52") (pin "K") (pinfunction "C_K") (pintype "passive"))
      (node (ref "LED54") (pin "A") (pinfunction "A_A") (pintype "passive"))
    )
    (net (code "112") (name "Net-(LED54-C)") (class "Default")
      (node (ref "JP5") (pin "12") (pinfunction "12_12") (pintype "passive"))
      (node (ref "LED54") (pin "K") (pinfunction "C_K") (pintype "passive"))
    )
    (net (code "113") (name "Net-(LED55-C)") (class "Default")
      (node (ref "LED55") (pin "K") (pinfunction "C_K") (pintype "passive"))
      (node (ref "LED56") (pin "A") (pinfunction "A_A") (pintype "passive"))
    )
    (net (code "114") (name "Net-(LED56-C)") (class "Default")
      (node (ref "LED56") (pin "K") (pinfunction "C_K") (pintype "passive"))
      (node (ref "LED57") (pin "A") (pinfunction "A_A") (pintype "passive"))
    )
    (net (code "115") (name "Net-(LED57-C)") (class "Default")
      (node (ref "JP5") (pin "5") (pinfunction "5_5") (pintype "passive"))
      (node (ref "LED57") (pin "K") (pinfunction "C_K") (pintype "passive"))
    )
    (net (code "116") (name "Net-(LED58-C)") (class "Default")
      (node (ref "LED58") (pin "K") (pinfunction "C_K") (pintype "passive"))
      (node (ref "LED59") (pin "A") (pinfunction "A_A") (pintype "passive"))
    )
    (net (code "117") (name "Net-(LED59-C)") (class "Default")
      (node (ref "LED59") (pin "K") (pinfunction "C_K") (pintype "passive"))
      (node (ref "LED60") (pin "A") (pinfunction "A_A") (pintype "passive"))
    )
    (net (code "118") (name "Net-(LED60-C)") (class "Default")
      (node (ref "JP5") (pin "7") (pinfunction "7_7") (pintype "passive"))
      (node (ref "LED60") (pin "K") (pinfunction "C_K") (pintype "passive"))
    )
    (net (code "119") (name "Net-(LED61-C)") (class "Default")
      (node (ref "LED61") (pin "K") (pinfunction "C_K") (pintype "passive"))
      (node (ref "LED62") (pin "A") (pinfunction "A_A") (pintype "passive"))
    )
    (net (code "120") (name "Net-(LED62-C)") (class "Default")
      (node (ref "LED62") (pin "K") (pinfunction "C_K") (pintype "passive"))
      (node (ref "LED63") (pin "A") (pinfunction "A_A") (pintype "passive"))
    )
    (net (code "121") (name "Net-(LED63-C)") (class "Default")
      (node (ref "JP5") (pin "9") (pinfunction "9_9") (pintype "passive"))
      (node (ref "LED63") (pin "K") (pinfunction "C_K") (pintype "passive"))
    )
    (net (code "122") (name "Net-(LED64-C)") (class "Default")
      (node (ref "LED64") (pin "K") (pinfunction "C_K") (pintype "passive"))
      (node (ref "LED65") (pin "A") (pinfunction "A_A") (pintype "passive"))
    )
    (net (code "123") (name "Net-(LED65-C)") (class "Default")
      (node (ref "LED65") (pin "K") (pinfunction "C_K") (pintype "passive"))
      (node (ref "LED66") (pin "A") (pinfunction "A_A") (pintype "passive"))
    )
    (net (code "124") (name "Net-(LED66-C)") (class "Default")
      (node (ref "JP5") (pin "11") (pinfunction "11_11") (pintype "passive"))
      (node (ref "LED66") (pin "K") (pinfunction "C_K") (pintype "passive"))
    )
    (net (code "125") (name "Net-(LED67-C)") (class "Default")
      (node (ref "LED67") (pin "K") (pinfunction "C_K") (pintype "passive"))
      (node (ref "LED68") (pin "A") (pinfunction "A_A") (pintype "passive"))
    )
    (net (code "126") (name "Net-(LED68-C)") (class "Default")
      (node (ref "LED68") (pin "K") (pinfunction "C_K") (pintype "passive"))
      (node (ref "LED69") (pin "A") (pinfunction "A_A") (pintype "passive"))
    )
    (net (code "127") (name "Net-(LED69-C)") (class "Default")
      (node (ref "JP5") (pin "13") (pinfunction "13_13") (pintype "passive"))
      (node (ref "LED69") (pin "K") (pinfunction "C_K") (pintype "passive"))
    )
    (net (code "128") (name "Net-(LED70-C)") (class "Default")
      (node (ref "LED70") (pin "K") (pinfunction "C_K") (pintype "passive"))
      (node (ref "LED71") (pin "A") (pinfunction "A_A") (pintype "passive"))
    )
    (net (code "129") (name "Net-(LED71-C)") (class "Default")
      (node (ref "LED71") (pin "K") (pinfunction "C_K") (pintype "passive"))
      (node (ref "LED72") (pin "A") (pinfunction "A_A") (pintype "passive"))
    )
    (net (code "130") (name "Net-(LED72-C)") (class "Default")
      (node (ref "JP5") (pin "15") (pinfunction "15_15") (pintype "passive"))
      (node (ref "LED72") (pin "K") (pinfunction "C_K") (pintype "passive"))
    )
    (net (code "131") (name "Net-(LED73-C)") (class "Default")
      (node (ref "LED73") (pin "K") (pinfunction "C_K") (pintype "passive"))
      (node (ref "LED74") (pin "A") (pinfunction "A_A") (pintype "passive"))
    )
    (net (code "132") (name "Net-(LED74-C)") (class "Default")
      (node (ref "LED74") (pin "K") (pinfunction "C_K") (pintype "passive"))
      (node (ref "LED75") (pin "A") (pinfunction "A_A") (pintype "passive"))
    )
    (net (code "133") (name "Net-(LED75-C)") (class "Default")
      (node (ref "JP5") (pin "17") (pinfunction "17_17") (pintype "passive"))
      (node (ref "LED75") (pin "K") (pinfunction "C_K") (pintype "passive"))
    )
    (net (code "134") (name "Net-(LED76-C)") (class "Default")
      (node (ref "LED76") (pin "K") (pinfunction "C_K") (pintype "passive"))
      (node (ref "LED77") (pin "A") (pinfunction "A_A") (pintype "passive"))
    )
    (net (code "135") (name "Net-(LED77-C)") (class "Default")
      (node (ref "LED77") (pin "K") (pinfunction "C_K") (pintype "passive"))
      (node (ref "LED78") (pin "A") (pinfunction "A_A") (pintype "passive"))
    )
    (net (code "136") (name "Net-(LED78-C)") (class "Default")
      (node (ref "JP5") (pin "19") (pinfunction "19_19") (pintype "passive"))
      (node (ref "LED78") (pin "K") (pinfunction "C_K") (pintype "passive"))
    )
    (net (code "137") (name "Net-(LED79-C)") (class "Default")
      (node (ref "LED79") (pin "K") (pinfunction "C_K") (pintype "passive"))
      (node (ref "LED80") (pin "A") (pinfunction "A_A") (pintype "passive"))
    )
    (net (code "138") (name "Net-(LED80-C)") (class "Default")
      (node (ref "LED80") (pin "K") (pinfunction "C_K") (pintype "passive"))
      (node (ref "LED81") (pin "A") (pinfunction "A_A") (pintype "passive"))
    )
    (net (code "139") (name "Net-(LED81-C)") (class "Default")
      (node (ref "JP5") (pin "20") (pinfunction "20_20") (pintype "passive"))
      (node (ref "LED81") (pin "K") (pinfunction "C_K") (pintype "passive"))
    )
    (net (code "140") (name "Net-(LED82-C)") (class "Default")
      (node (ref "LED82") (pin "K") (pinfunction "C_K") (pintype "passive"))
      (node (ref "LED86") (pin "A") (pinfunction "A_A") (pintype "passive"))
    )
    (net (code "141") (name "Net-(LED83-C)") (class "Default")
      (node (ref "LED83") (pin "K") (pinfunction "C_K") (pintype "passive"))
      (node (ref "LED84") (pin "A") (pinfunction "A_A") (pintype "passive"))
    )
    (net (code "142") (name "Net-(LED84-C)") (class "Default")
      (node (ref "JP5") (pin "8") (pinfunction "8_8") (pintype "passive"))
      (node (ref "LED84") (pin "K") (pinfunction "C_K") (pintype "passive"))
    )
    (net (code "143") (name "Net-(LED85-C)") (class "Default")
      (node (ref "JP5") (pin "6") (pinfunction "6_6") (pintype "passive"))
      (node (ref "LED85") (pin "K") (pinfunction "C_K") (pintype "passive"))
    )
    (net (code "144") (name "Net-(LED86-C)") (class "Default")
      (node (ref "LED85") (pin "A") (pinfunction "A_A") (pintype "passive"))
      (node (ref "LED86") (pin "K") (pinfunction "C_K") (pintype "passive"))
    )
    (net (code "145") (name "Net-(LED87-C)") (class "Default")
      (node (ref "LED83") (pin "A") (pinfunction "A_A") (pintype "passive"))
      (node (ref "LED87") (pin "K") (pinfunction "C_K") (pintype "passive"))
    )
    (net (code "146") (name "Net-(LED88-C)") (class "Default")
      (node (ref "LED88") (pin "K") (pinfunction "C_K") (pintype "passive"))
      (node (ref "LED89") (pin "A") (pinfunction "A_A") (pintype "passive"))
    )
    (net (code "147") (name "Net-(LED89-C)") (class "Default")
      (node (ref "LED89") (pin "K") (pinfunction "C_K") (pintype "passive"))
      (node (ref "LED90") (pin "A") (pinfunction "A_A") (pintype "passive"))
    )
    (net (code "148") (name "Net-(LED90-C)") (class "Default")
      (node (ref "JP5") (pin "4") (pinfunction "4_4") (pintype "passive"))
      (node (ref "LED90") (pin "K") (pinfunction "C_K") (pintype "passive"))
    )
    (net (code "149") (name "Net-(LED91-C)") (class "Default")
      (node (ref "JP5") (pin "2") (pinfunction "2_2") (pintype "passive"))
      (node (ref "LED91") (pin "K") (pinfunction "C_K") (pintype "passive"))
    )
    (net (code "150") (name "Net-(LED92-C)") (class "Default")
      (node (ref "LED91") (pin "A") (pinfunction "A_A") (pintype "passive"))
      (node (ref "LED92") (pin "K") (pinfunction "C_K") (pintype "passive"))
    )
    (net (code "151") (name "Net-(LED93-C)") (class "Default")
      (node (ref "LED92") (pin "A") (pinfunction "A_A") (pintype "passive"))
      (node (ref "LED93") (pin "K") (pinfunction "C_K") (pintype "passive"))
    )
    (net (code "152") (name "Net-(LED94-C)") (class "Default")
      (node (ref "LED94") (pin "K") (pinfunction "C_K") (pintype "passive"))
      (node (ref "LED95") (pin "A") (pinfunction "A_A") (pintype "passive"))
    )
    (net (code "153") (name "Net-(LED95-C)") (class "Default")
      (node (ref "LED95") (pin "K") (pinfunction "C_K") (pintype "passive"))
      (node (ref "LED96") (pin "A") (pinfunction "A_A") (pintype "passive"))
    )
    (net (code "154") (name "Net-(LED96-C)") (class "Default")
      (node (ref "JP5") (pin "1") (pinfunction "1_1") (pintype "passive"))
      (node (ref "LED96") (pin "K") (pinfunction "C_K") (pintype "passive"))
    )
    (net (code "155") (name "Net-(LED97-C)") (class "Default")
      (node (ref "JP5") (pin "3") (pinfunction "3_3") (pintype "passive"))
      (node (ref "LED97") (pin "K") (pinfunction "C_K") (pintype "passive"))
    )
    (net (code "156") (name "Net-(LED98-C)") (class "Default")
      (node (ref "LED97") (pin "A") (pinfunction "A_A") (pintype "passive"))
      (node (ref "LED98") (pin "K") (pinfunction "C_K") (pintype "passive"))
    )
    (net (code "157") (name "Net-(LED99-C)") (class "Default")
      (node (ref "LED98") (pin "A") (pinfunction "A_A") (pintype "passive"))
      (node (ref "LED99") (pin "K") (pinfunction "C_K") (pintype "passive"))
    )
    (net (code "158") (name "Net-(LED100-C)") (class "Default")
      (node (ref "LED100") (pin "K") (pinfunction "C_K") (pintype "passive"))
      (node (ref "LED101") (pin "A") (pinfunction "A_A") (pintype "passive"))
    )
    (net (code "159") (name "Net-(LED101-C)") (class "Default")
      (node (ref "JP2") (pin "13") (pinfunction "13_13") (pintype "passive"))
      (node (ref "LED101") (pin "K") (pinfunction "C_K") (pintype "passive"))
    )
    (net (code "160") (name "Net-(LED102-C)") (class "Default")
      (node (ref "LED102") (pin "K") (pinfunction "C_K") (pintype "passive"))
      (node (ref "LED103") (pin "A") (pinfunction "A_A") (pintype "passive"))
    )
    (net (code "161") (name "Net-(LED103-C)") (class "Default")
      (node (ref "JP2") (pin "11") (pinfunction "11_11") (pintype "passive"))
      (node (ref "LED103") (pin "K") (pinfunction "C_K") (pintype "passive"))
    )
    (net (code "162") (name "Net-(LED104-C)") (class "Default")
      (node (ref "LED104") (pin "K") (pinfunction "C_K") (pintype "passive"))
      (node (ref "LED105") (pin "A") (pinfunction "A_A") (pintype "passive"))
    )
    (net (code "163") (name "Net-(LED105-C)") (class "Default")
      (node (ref "JP2") (pin "9") (pinfunction "9_9") (pintype "passive"))
      (node (ref "LED105") (pin "K") (pinfunction "C_K") (pintype "passive"))
    )
    (net (code "164") (name "Net-(LED106-C)") (class "Default")
      (node (ref "LED106") (pin "K") (pinfunction "C_K") (pintype "passive"))
      (node (ref "LED107") (pin "A") (pinfunction "A_A") (pintype "passive"))
    )
    (net (code "165") (name "Net-(LED107-C)") (class "Default")
      (node (ref "JP2") (pin "7") (pinfunction "7_7") (pintype "passive"))
      (node (ref "LED107") (pin "K") (pinfunction "C_K") (pintype "passive"))
    )
    (net (code "166") (name "unconnected-(2LED-SDO-Pad14)") (class "Default")
      (node (ref "2LED") (pin "14") (pinfunction "SDO_14") (pintype "bidirectional"))
    )
    (net (code "167") (name "unconnected-(2LED-{slash}OUT4-Pad9)") (class "Default")
      (node (ref "2LED") (pin "9") (pinfunction "/OUT4_9") (pintype "output"))
    )
    (net (code "168") (name "unconnected-(2LED-{slash}OUT5-Pad10)") (class "Default")
      (node (ref "2LED") (pin "10") (pinfunction "/OUT5_10") (pintype "output"))
    )
    (net (code "169") (name "unconnected-(2LED-{slash}OUT6-Pad11)") (class "Default")
      (node (ref "2LED") (pin "11") (pinfunction "/OUT6_11") (pintype "output"))
    )
    (net (code "170") (name "unconnected-(2LED-{slash}OUT7-Pad12)") (class "Default")
      (node (ref "2LED") (pin "12") (pinfunction "/OUT7_12") (pintype "output"))
    )
    (net (code "171") (name "unconnected-(3LED3-{slash}OUT1-Pad6)") (class "Default")
      (node (ref "3LED3") (pin "6") (pinfunction "/OUT1_6") (pintype "output"))
    )
    (net (code "172") (name "unconnected-(3LED3-{slash}OUT2-Pad7)") (class "Default")
      (node (ref "3LED3") (pin "7") (pinfunction "/OUT2_7") (pintype "output"))
    )
    (net (code "173") (name "unconnected-(3LED3-{slash}OUT3-Pad8)") (class "Default")
      (node (ref "3LED3") (pin "8") (pinfunction "/OUT3_8") (pintype "output"))
    )
    (net (code "174") (name "unconnected-(3LED3-{slash}OUT4-Pad9)") (class "Default")
      (node (ref "3LED3") (pin "9") (pinfunction "/OUT4_9") (pintype "output"))
    )
    (net (code "175") (name "unconnected-(3LED3-{slash}OUT5-Pad10)") (class "Default")
      (node (ref "3LED3") (pin "10") (pinfunction "/OUT5_10") (pintype "output"))
    )
    (net (code "176") (name "unconnected-(3LED3-{slash}OUT6-Pad11)") (class "Default")
      (node (ref "3LED3") (pin "11") (pinfunction "/OUT6_11") (pintype "output"))
    )
    (net (code "177") (name "unconnected-(3LED3-{slash}OUT7-Pad12)") (class "Default")
      (node (ref "3LED3") (pin "12") (pinfunction "/OUT7_12") (pintype "output"))
    )
    (net (code "178") (name "unconnected-(4LED2-{slash}OUT2-Pad7)") (class "Default")
      (node (ref "4LED2") (pin "7") (pinfunction "/OUT2_7") (pintype "output"))
    )
    (net (code "179") (name "unconnected-(4LED2-{slash}OUT3-Pad8)") (class "Default")
      (node (ref "4LED2") (pin "8") (pinfunction "/OUT3_8") (pintype "output"))
    )
    (net (code "180") (name "unconnected-(4LED2-{slash}OUT4-Pad9)") (class "Default")
      (node (ref "4LED2") (pin "9") (pinfunction "/OUT4_9") (pintype "output"))
    )
    (net (code "181") (name "unconnected-(4LED2-{slash}OUT5-Pad10)") (class "Default")
      (node (ref "4LED2") (pin "10") (pinfunction "/OUT5_10") (pintype "output"))
    )
    (net (code "182") (name "unconnected-(4LED2-{slash}OUT6-Pad11)") (class "Default")
      (node (ref "4LED2") (pin "11") (pinfunction "/OUT6_11") (pintype "output"))
    )
    (net (code "183") (name "unconnected-(4LED2-{slash}OUT7-Pad12)") (class "Default")
      (node (ref "4LED2") (pin "12") (pinfunction "/OUT7_12") (pintype "output"))
    )
    (net (code "184") (name "unconnected-(IC1-NC-Pad5)") (class "Default")
      (node (ref "IC1") (pin "5") (pinfunction "NC_5") (pintype "bidirectional"))
    )
    (net (code "185") (name "unconnected-(IC1-{slash}INT0-Pad6)") (class "Default")
      (node (ref "IC1") (pin "6") (pinfunction "/INT0_6") (pintype "output"))
    )
    (net (code "186") (name "unconnected-(IC1-{slash}INT1-Pad7)") (class "Default")
      (node (ref "IC1") (pin "7") (pinfunction "/INT1_7") (pintype "output"))
    )
    (net (code "187") (name "unconnected-(IC1-{slash}PF-Pad15)") (class "Default")
      (node (ref "IC1") (pin "15") (pinfunction "/PF_15") (pintype "output"))
    )
    (net (code "188") (name "unconnected-(JP4-Pad6)") (class "Default")
      (node (ref "JP4") (pin "6") (pinfunction "6_6") (pintype "passive"))
    )
    (net (code "189") (name "unconnected-(JP5-Pad14)") (class "Default")
      (node (ref "JP5") (pin "14") (pinfunction "14_14") (pintype "passive"))
    )
    (net (code "190") (name "unconnected-(JP5-Pad16)") (class "Default")
      (node (ref "JP5") (pin "16") (pinfunction "16_16") (pintype "passive"))
    )
    (net (code "191") (name "unconnected-(JP5-Pad18)") (class "Default")
      (node (ref "JP5") (pin "18") (pinfunction "18_18") (pintype "passive"))
    )
    (net (code "192") (name "unconnected-(JP6-Pad14)") (class "Default")
      (node (ref "JP6") (pin "14") (pinfunction "14_14") (pintype "passive"))
    )
    (net (code "193") (name "unconnected-(JP6-Pad16)") (class "Default")
      (node (ref "JP6") (pin "16") (pinfunction "16_16") (pintype "passive"))
    )
    (net (code "194") (name "unconnected-(JP6-Pad18)") (class "Default")
      (node (ref "JP6") (pin "18") (pinfunction "18_18") (pintype "passive"))
    )
    (net (code "195") (name "unconnected-(JP7-Pad3)") (class "Default")
      (node (ref "JP7") (pin "3") (pinfunction "3_3") (pintype "passive"))
    )
    (net (code "196") (name "unconnected-(JP7-Pad6)") (class "Default")
      (node (ref "JP7") (pin "6") (pinfunction "6_6") (pintype "passive"))
    )
    (net (code "197") (name "unconnected-(JP8-Pad1)") (class "Default")
      (node (ref "JP8") (pin "1") (pinfunction "1_1") (pintype "passive"))
    )
    (net (code "198") (name "unconnected-(JP8-Pad2)") (class "Default")
      (node (ref "JP8") (pin "2") (pinfunction "2_2") (pintype "passive"))
    )
    (net (code "199") (name "unconnected-(JP8-Pad3)") (class "Default")
      (node (ref "JP8") (pin "3") (pinfunction "3_3") (pintype "passive"))
    )
    (net (code "200") (name "unconnected-(JP8-Pad6)") (class "Default")
      (node (ref "JP8") (pin "6") (pinfunction "6_6") (pintype "passive"))
    )
    (net (code "201") (name "unconnected-(JP8-Pad7)") (class "Default")
      (node (ref "JP8") (pin "7") (pinfunction "7_7") (pintype "passive"))
    )
    (net (code "202") (name "unconnected-(JP9-Pad6)") (class "Default")
      (node (ref "JP9") (pin "6") (pinfunction "6_6") (pintype "passive"))
    )
    (net (code "203") (name "unconnected-(JP10-Pad3)") (class "Default")
      (node (ref "JP10") (pin "3") (pinfunction "3_3") (pintype "passive"))
    )
    (net (code "204") (name "unconnected-(JP10-Pad4)") (class "Default")
      (node (ref "JP10") (pin "4") (pinfunction "4_4") (pintype "passive"))
    )
    (net (code "205") (name "unconnected-(JP10-Pad5)") (class "Default")
      (node (ref "JP10") (pin "5") (pinfunction "5_5") (pintype "passive"))
    )
    (net (code "206") (name "unconnected-(R12-Pad2)") (class "Default")
      (node (ref "R12") (pin "2") (pinfunction "2_2") (pintype "passive"))
    )
    (net (code "207") (name "unconnected-(S1-Pad1B)") (class "Default")
      (node (ref "S1") (pin "1B") (pinfunction "1B_1B") (pintype "passive"))
    )
    (net (code "208") (name "unconnected-(S1-PadNC)") (class "Default")
      (node (ref "S1") (pin "NC") (pinfunction "NC_NC") (pintype "passive"))
    )
    (net (code "209") (name "unconnected-(S3-Pad1B)") (class "Default")
      (node (ref "S3") (pin "1B") (pinfunction "1B_1B") (pintype "passive"))
    )
    (net (code "210") (name "unconnected-(S3-PadNC)") (class "Default")
      (node (ref "S3") (pin "NC") (pinfunction "NC_NC") (pintype "passive"))
    )
  )
)
